# Arch_Max.net
KiCad netlist of a schematic drawn in EAGLE
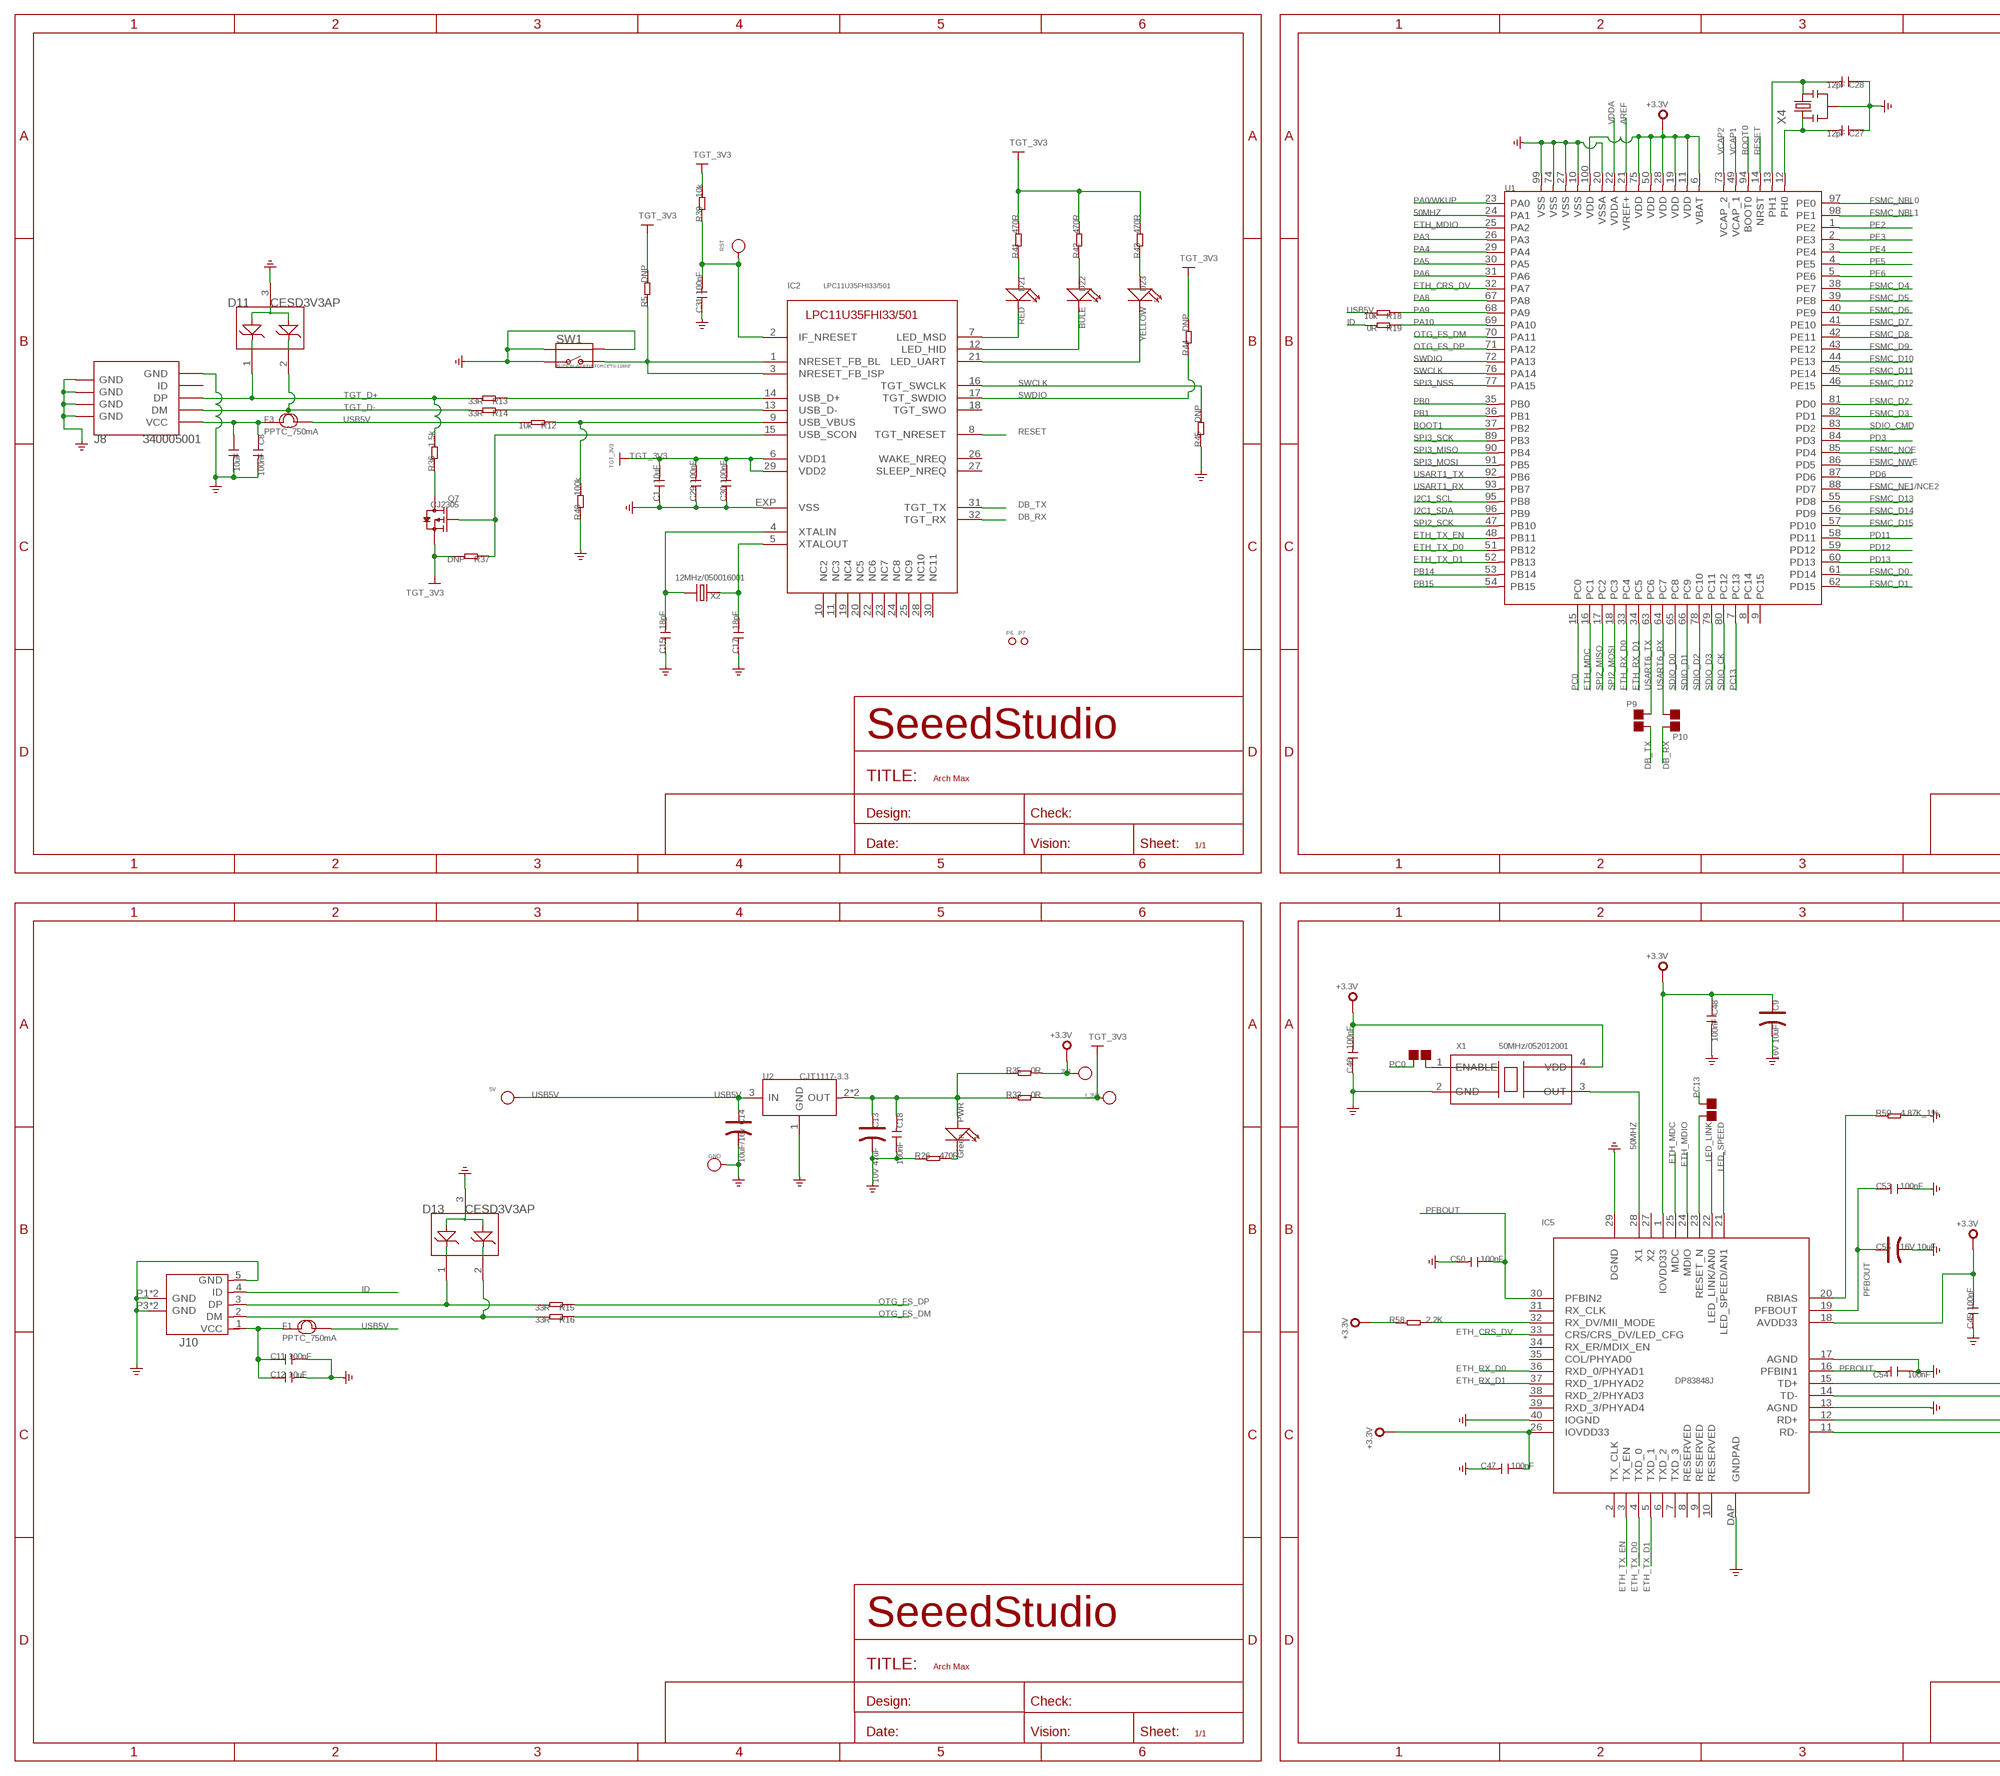
[diagram p0: schematic, sheet 1, part 1 of 2]
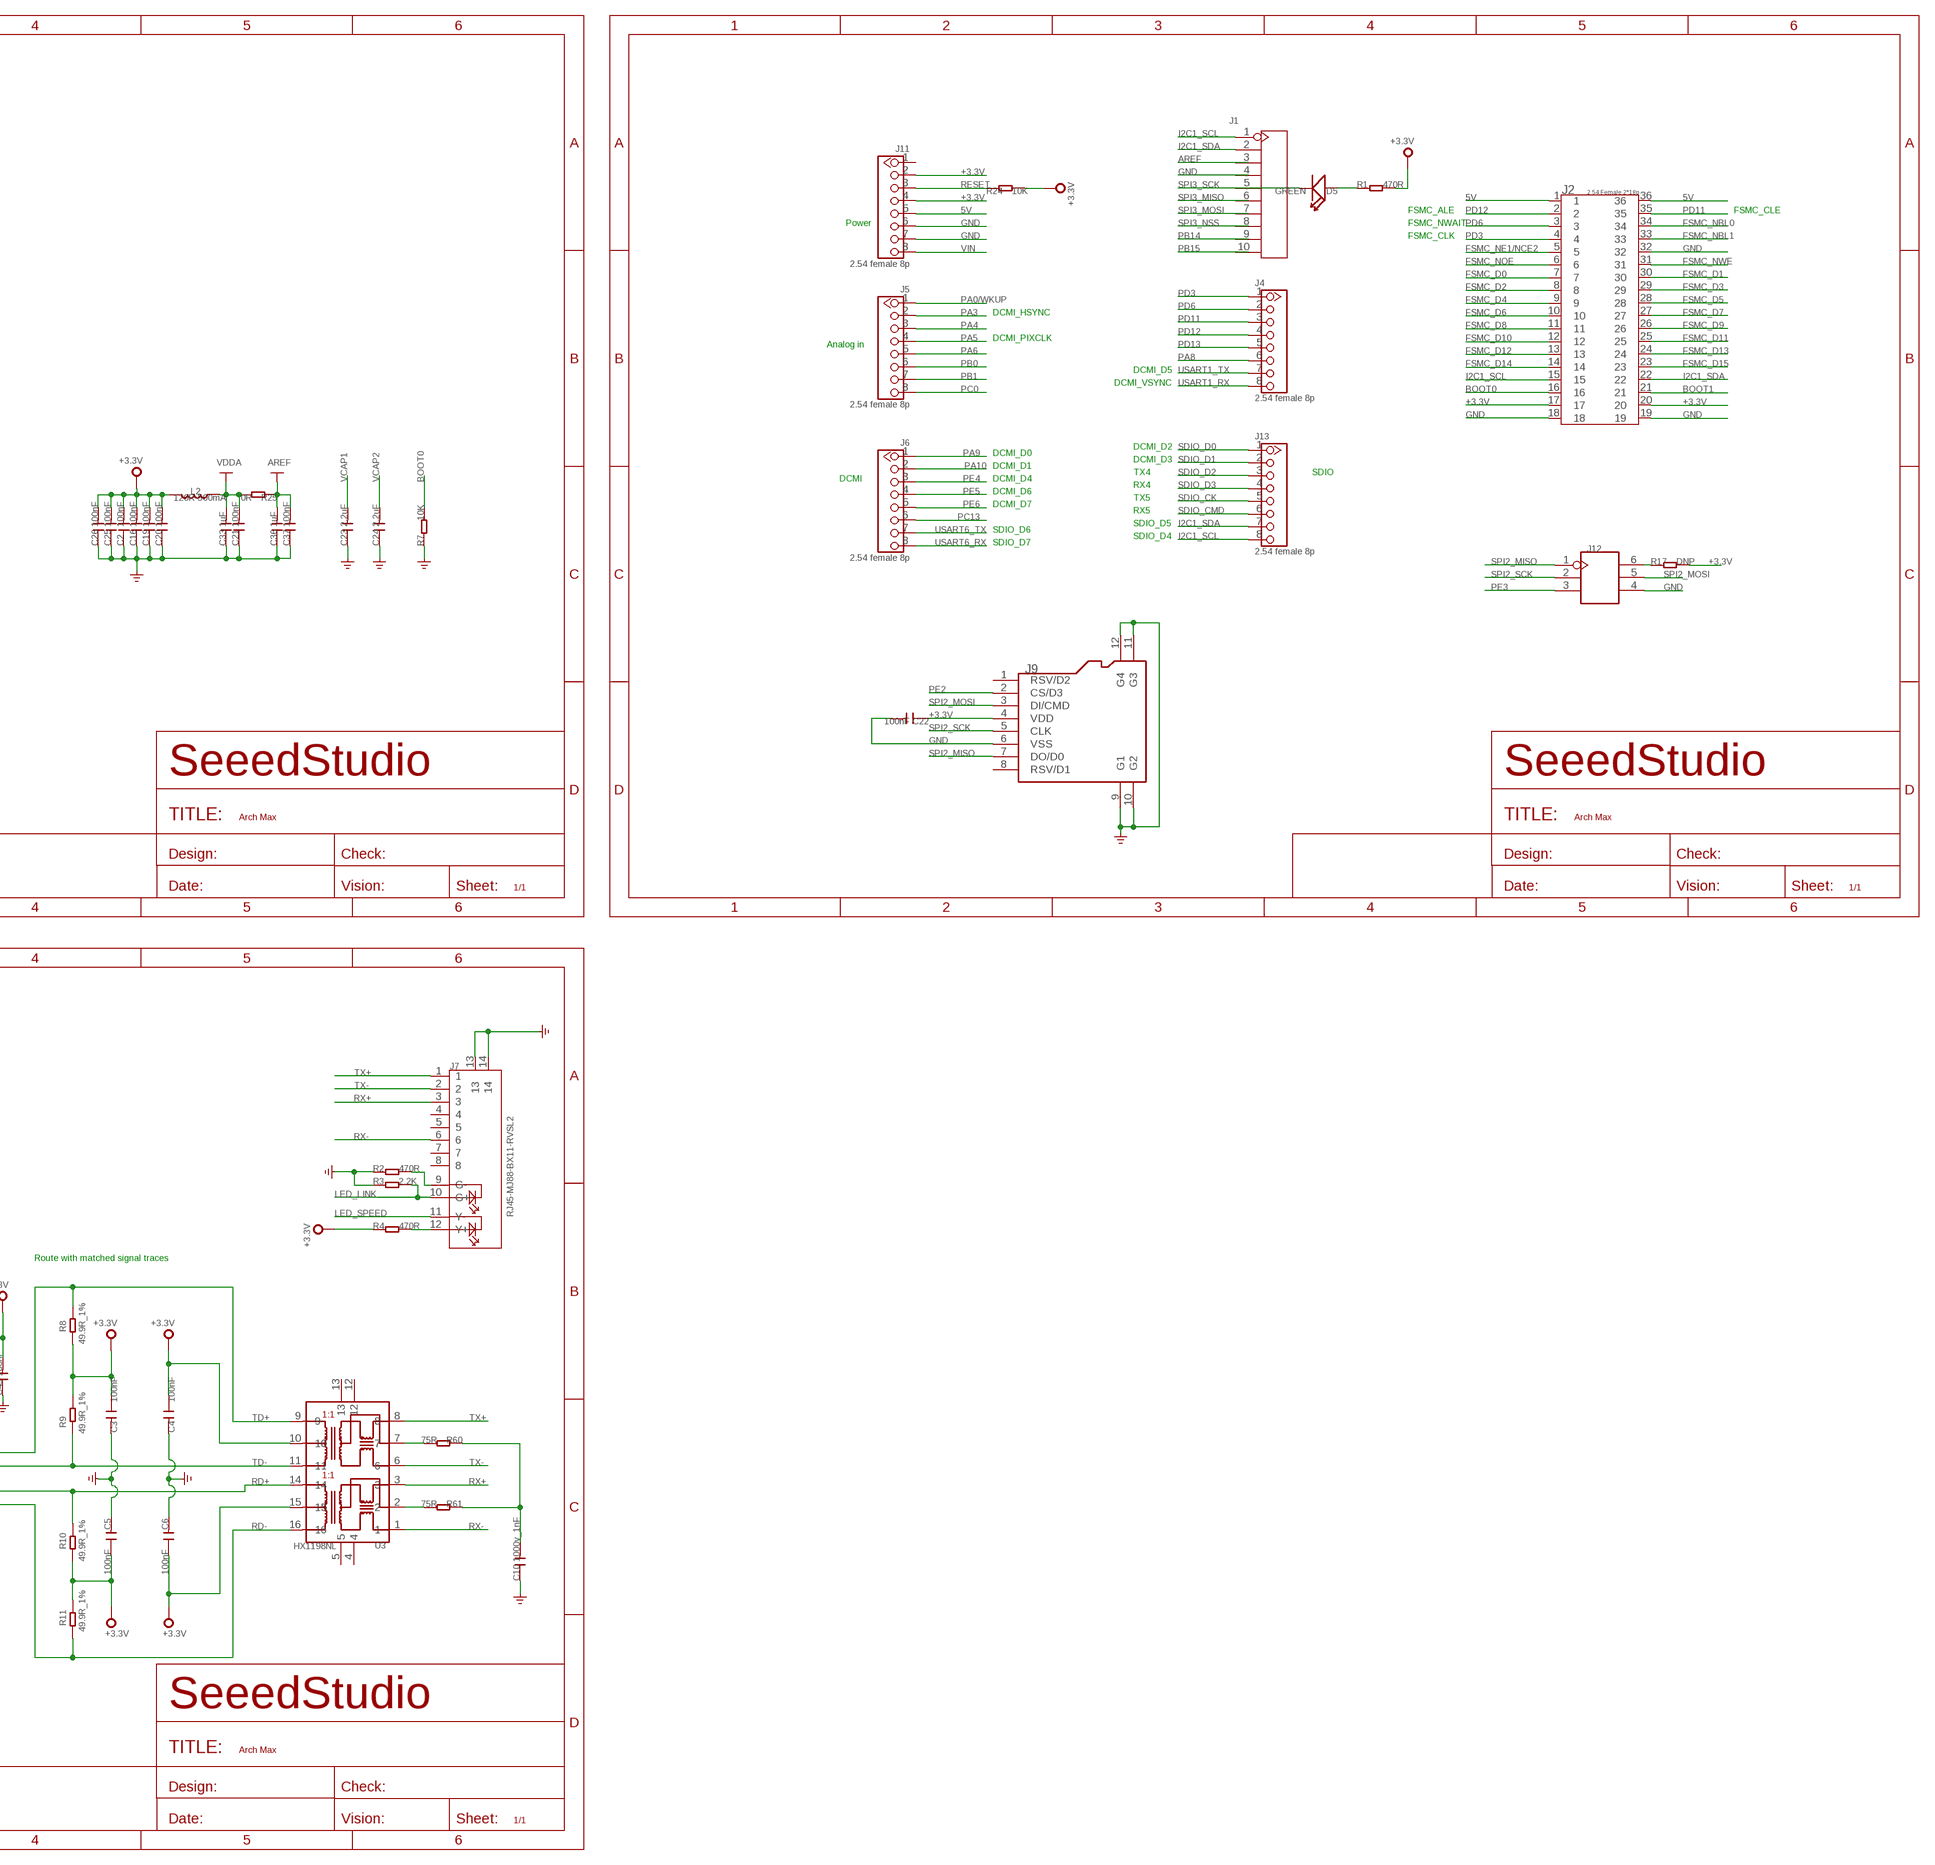
[diagram p1: schematic, sheet 1, part 2 of 2]

(export (version "E")
  (design (tool "Eeschema 10.0.6"))
  (components
    (comp (ref "3V3")
      (value "PAD-TEST-POINT'4545'")
      (footprint "eagle-import:TP_4545")
      (fields (field (name "PARTNO") "DNP"))
      (libsource (lib "eagle-import") (part "PAD-TEST-POINT'4545'"))
    )
    (comp (ref "5V")
      (value "PAD-TEST-POINT'4545'")
      (footprint "eagle-import:TP_4545")
      (fields (field (name "PARTNO") "DNP"))
      (libsource (lib "eagle-import") (part "PAD-TEST-POINT'4545'"))
    )
    (comp (ref "C1")
      (value "10uF")
      (footprint "eagle-import:C0805")
      (libsource (lib "eagle-import") (part "C-0805"))
    )
    (comp (ref "C2")
      (value "100nF")
      (footprint "eagle-import:C0603")
      (libsource (lib "eagle-import") (part "C-0603"))
    )
    (comp (ref "C3")
      (value "100nF")
      (footprint "eagle-import:C0603")
      (libsource (lib "eagle-import") (part "C-0603"))
    )
    (comp (ref "C4")
      (value "100nF")
      (footprint "eagle-import:C0603")
      (libsource (lib "eagle-import") (part "C-0603"))
    )
    (comp (ref "C5")
      (value "100nF")
      (footprint "eagle-import:C0603")
      (libsource (lib "eagle-import") (part "C-0603"))
    )
    (comp (ref "C6")
      (value "100nF")
      (footprint "eagle-import:C0603")
      (libsource (lib "eagle-import") (part "C-0603"))
    )
    (comp (ref "C7")
      (value "10uF")
      (footprint "eagle-import:C0805")
      (libsource (lib "eagle-import") (part "C-0805"))
    )
    (comp (ref "C8")
      (value "100nF")
      (footprint "eagle-import:C0603")
      (libsource (lib "eagle-import") (part "C-0603"))
    )
    (comp (ref "C9")
      (value "16V 10uF")
      (footprint "eagle-import:AVX-A")
      (libsource (lib "eagle-import") (part "CAP-AVX-A"))
    )
    (comp (ref "C10")
      (value "1000v_1nF")
      (footprint "eagle-import:C1206")
      (libsource (lib "eagle-import") (part "C-1206"))
    )
    (comp (ref "C11")
      (value "100nF")
      (footprint "eagle-import:C0603")
      (libsource (lib "eagle-import") (part "C-0603"))
    )
    (comp (ref "C12")
      (value "10uF")
      (footprint "eagle-import:C0805")
      (libsource (lib "eagle-import") (part "C-0805"))
    )
    (comp (ref "C13")
      (value "10V 47uF")
      (footprint "eagle-import:AVX-B")
      (libsource (lib "eagle-import") (part "CAP-AVX-B"))
    )
    (comp (ref "C14")
      (value "10uF/16v")
      (footprint "eagle-import:AVX-A")
      (libsource (lib "eagle-import") (part "CAP-AVX-A"))
    )
    (comp (ref "C15")
      (value "18pF")
      (footprint "eagle-import:C0603")
      (libsource (lib "eagle-import") (part "C-0603"))
    )
    (comp (ref "C16")
      (value "100nF")
      (footprint "eagle-import:C0603")
      (libsource (lib "eagle-import") (part "C-0603"))
    )
    (comp (ref "C17")
      (value "18pF")
      (footprint "eagle-import:C0603")
      (libsource (lib "eagle-import") (part "C-0603"))
    )
    (comp (ref "C18")
      (value "100nF")
      (footprint "eagle-import:C0603")
      (libsource (lib "eagle-import") (part "C-0603"))
    )
    (comp (ref "C19")
      (value "100nF")
      (footprint "eagle-import:C0603")
      (libsource (lib "eagle-import") (part "C-0603"))
    )
    (comp (ref "C20")
      (value "100nF")
      (footprint "eagle-import:C0603")
      (libsource (lib "eagle-import") (part "C-0603"))
    )
    (comp (ref "C21")
      (value "100nF")
      (footprint "eagle-import:C0603")
      (libsource (lib "eagle-import") (part "C-0603"))
    )
    (comp (ref "C22")
      (value "100nF")
      (footprint "eagle-import:C0603")
      (libsource (lib "eagle-import") (part "C-0603"))
    )
    (comp (ref "C23")
      (value "2.2uF")
      (footprint "eagle-import:C0603")
      (libsource (lib "eagle-import") (part "C-0603"))
    )
    (comp (ref "C24")
      (value "2.2uF")
      (footprint "eagle-import:C0603")
      (libsource (lib "eagle-import") (part "C-0603"))
    )
    (comp (ref "C25")
      (value "100nF")
      (footprint "eagle-import:C0603")
      (libsource (lib "eagle-import") (part "C-0603"))
    )
    (comp (ref "C26")
      (value "100nF")
      (footprint "eagle-import:C0603")
      (libsource (lib "eagle-import") (part "C-0603"))
    )
    (comp (ref "C27")
      (value "12pF")
      (footprint "eagle-import:C0603")
      (libsource (lib "eagle-import") (part "C-0603"))
    )
    (comp (ref "C28")
      (value "12pF")
      (footprint "eagle-import:C0603")
      (libsource (lib "eagle-import") (part "C-0603"))
    )
    (comp (ref "C29")
      (value "100nF")
      (footprint "eagle-import:C0603")
      (libsource (lib "eagle-import") (part "C-0603"))
    )
    (comp (ref "C30")
      (value "100nF")
      (footprint "eagle-import:C0603")
      (libsource (lib "eagle-import") (part "C-0603"))
    )
    (comp (ref "C31")
      (value "100nF")
      (footprint "eagle-import:C0603")
      (libsource (lib "eagle-import") (part "C-0603"))
    )
    (comp (ref "C33")
      (value "1uF")
      (footprint "eagle-import:C0603")
      (libsource (lib "eagle-import") (part "C-0603"))
    )
    (comp (ref "C36")
      (value "1uF")
      (footprint "eagle-import:C0603")
      (libsource (lib "eagle-import") (part "C-0603"))
    )
    (comp (ref "C37")
      (value "100nF")
      (footprint "eagle-import:C0603")
      (libsource (lib "eagle-import") (part "C-0603"))
    )
    (comp (ref "C45")
      (value "100nF")
      (footprint "eagle-import:C0603")
      (libsource (lib "eagle-import") (part "C-0603"))
    )
    (comp (ref "C46")
      (value "100nF")
      (footprint "eagle-import:C0603")
      (libsource (lib "eagle-import") (part "C-0603"))
    )
    (comp (ref "C47")
      (value "100nF")
      (footprint "eagle-import:C0603")
      (libsource (lib "eagle-import") (part "C-0603"))
    )
    (comp (ref "C48")
      (value "100nF")
      (footprint "eagle-import:C0603")
      (libsource (lib "eagle-import") (part "C-0603"))
    )
    (comp (ref "C50")
      (value "100nF")
      (footprint "eagle-import:C0603")
      (libsource (lib "eagle-import") (part "C-0603"))
    )
    (comp (ref "C53")
      (value "100nF")
      (footprint "eagle-import:C0603")
      (libsource (lib "eagle-import") (part "C-0603"))
    )
    (comp (ref "C54")
      (value "100nF")
      (footprint "eagle-import:C0603")
      (libsource (lib "eagle-import") (part "C-0603"))
    )
    (comp (ref "C55")
      (value "16V 10uF")
      (footprint "eagle-import:AVX-A")
      (libsource (lib "eagle-import") (part "CAP-AVX-A"))
    )
    (comp (ref "D5")
      (value "GREEN")
      (footprint "eagle-import:LED-0603")
      (libsource (lib "eagle-import") (part "LED'0603'"))
    )
    (comp (ref "D11")
      (value "CESD3V3AP")
      (footprint "eagle-import:SOT23")
      (libsource (lib "eagle-import") (part "D-ESD-3P"))
    )
    (comp (ref "D13")
      (value "CESD3V3AP")
      (footprint "eagle-import:SOT23")
      (libsource (lib "eagle-import") (part "D-ESD-3P"))
    )
    (comp (ref "D21")
      (value "RED")
      (footprint "eagle-import:LED-0603")
      (libsource (lib "eagle-import") (part "LED'0603'"))
    )
    (comp (ref "D22")
      (value "BULE")
      (footprint "eagle-import:LED-0603")
      (libsource (lib "eagle-import") (part "LED'0603'"))
    )
    (comp (ref "D23")
      (value "YELLOW")
      (footprint "eagle-import:LED-0603")
      (libsource (lib "eagle-import") (part "LED'0603'"))
    )
    (comp (ref "F1")
      (value "PPTC_750mA")
      (footprint "eagle-import:F1206")
      (libsource (lib "eagle-import") (part "FUSE'1206'"))
    )
    (comp (ref "F3")
      (value "PPTC_750mA")
      (footprint "eagle-import:F1206")
      (libsource (lib "eagle-import") (part "FUSE'1206'"))
    )
    (comp (ref "GND")
      (value "PAD-TEST-POINT'4545'")
      (footprint "eagle-import:TP_4545")
      (fields (field (name "PARTNO") "DNP"))
      (libsource (lib "eagle-import") (part "PAD-TEST-POINT'4545'"))
    )
    (comp (ref "IC2")
      (value "LPC11U35FHI33/501")
      (footprint "eagle-import:MBED-ICS_HVQFN33")
      (libsource (lib "eagle-import") (part "MBED-ICS_IF-LPC11U35"))
    )
    (comp (ref "IC5")
      (value "DP83848J")
      (footprint "eagle-import:LLP-40")
      (libsource (lib "eagle-import") (part "DP83848J"))
    )
    (comp (ref "I_3V3")
      (value "PAD-TEST-POINT'4545'")
      (footprint "eagle-import:TP_4545")
      (fields (field (name "PARTNO") "DNP"))
      (libsource (lib "eagle-import") (part "PAD-TEST-POINT'4545'"))
    )
    (comp (ref "J1")
      (value "HEADER-10P-2.54")
      (footprint "eagle-import:10P-2.54-65_35MIL")
      (libsource (lib "eagle-import") (part "HEADER-10P-2.54"))
    )
    (comp (ref "J2")
      (value "2.54 Female 2*18p")
      (footprint "eagle-import:2.54-2X18P")
      (libsource (lib "eagle-import") (part "HEADER-2X18P"))
    )
    (comp (ref "J4")
      (value "2.54 female 8p")
      (footprint "eagle-import:CK_1X8")
      (libsource (lib "eagle-import") (part "HEADER-8P2.54"))
    )
    (comp (ref "J5")
      (value "2.54 female 8p")
      (footprint "eagle-import:CK_1X8")
      (libsource (lib "eagle-import") (part "HEADER-8P2.54"))
    )
    (comp (ref "J6")
      (value "2.54 female 8p")
      (footprint "eagle-import:CK_1X8")
      (libsource (lib "eagle-import") (part "HEADER-8P2.54"))
    )
    (comp (ref "J7")
      (value "RJ45-MJ88-BX11-RVSL2")
      (footprint "eagle-import:RJ45-MJ88-BX11-RVSL2")
      (libsource (lib "eagle-import") (part "RJ45-MJ88-BX11-RVSL2"))
    )
    (comp (ref "J8")
      (value "340005001")
      (footprint "eagle-import:MICRO-USB")
      (libsource (lib "eagle-import") (part "USB-MINIUSB-5P-MICRO"))
    )
    (comp (ref "J9")
      (value "HOLDER-MICROSD-8P")
      (footprint "eagle-import:8P-SMD")
      (libsource (lib "eagle-import") (part "HOLDER-MICROSD-8P"))
    )
    (comp (ref "J10")
      (value "USB-MICRO-5P'AB'")
      (footprint "eagle-import:MICRO-USB-5P-AB")
      (libsource (lib "eagle-import") (part "USB-MICRO-5P'AB'"))
    )
    (comp (ref "J11")
      (value "2.54 female 8p")
      (footprint "eagle-import:CK_1X8")
      (libsource (lib "eagle-import") (part "HEADER-8P2.54"))
    )
    (comp (ref "J12")
      (value "HEADER-2X3P-65/35MIL")
      (footprint "eagle-import:2X3P-2.54-65_35MIL")
      (libsource (lib "eagle-import") (part "HEADER-2X3P-65/35MIL"))
    )
    (comp (ref "J13")
      (value "2.54 female 8p")
      (footprint "eagle-import:CK_1X8")
      (libsource (lib "eagle-import") (part "HEADER-8P2.54"))
    )
    (comp (ref "L2")
      (value "120R-500mA")
      (footprint "eagle-import:L0603")
      (libsource (lib "eagle-import") (part "L'0603'"))
    )
    (comp (ref "P1")
      (value "PAD-JUMPER-2P")
      (footprint "eagle-import:2P-SMD-1.78X1.27")
      (fields (field (name "PARTNO") "DNP"))
      (libsource (lib "eagle-import") (part "PAD-JUMPER-2P"))
    )
    (comp (ref "P5")
      (value "PAD-JUMPER-2P")
      (footprint "eagle-import:2P-SMD-1.78X1.27")
      (fields (field (name "PARTNO") "DNP"))
      (libsource (lib "eagle-import") (part "PAD-JUMPER-2P"))
    )
    (comp (ref "P6")
      (value "PAD-MARK'ANNULAR'")
      (footprint "eagle-import:ROUND-MARK-1.0")
      (fields (field (name "PARTNO") "DNP"))
      (libsource (lib "eagle-import") (part "PAD-MARK'ANNULAR'"))
    )
    (comp (ref "P7")
      (value "PAD-MARK'ANNULAR'")
      (footprint "eagle-import:ROUND-MARK-1.0")
      (fields (field (name "PARTNO") "DNP"))
      (libsource (lib "eagle-import") (part "PAD-MARK'ANNULAR'"))
    )
    (comp (ref "P9")
      (value "PAD-JUMPER-2P")
      (footprint "eagle-import:2P-SMD-1.78X1.27")
      (fields (field (name "PARTNO") "DNP"))
      (libsource (lib "eagle-import") (part "PAD-JUMPER-2P"))
    )
    (comp (ref "P10")
      (value "PAD-JUMPER-2P")
      (footprint "eagle-import:2P-SMD-1.78X1.27")
      (fields (field (name "PARTNO") "DNP"))
      (libsource (lib "eagle-import") (part "PAD-JUMPER-2P"))
    )
    (comp (ref "PWR")
      (value "Green")
      (footprint "eagle-import:LED-0603")
      (libsource (lib "eagle-import") (part "LED'0603'"))
    )
    (comp (ref "Q7")
      (value "CJ2305")
      (footprint "eagle-import:SOT23")
      (libsource (lib "eagle-import") (part "MOSFET-P'SI2323CDS/SI2305DS{lt}BR{gt}'"))
    )
    (comp (ref "R1")
      (value "470R")
      (footprint "eagle-import:R0603")
      (libsource (lib "eagle-import") (part "R-0603"))
    )
    (comp (ref "R2")
      (value "470R")
      (footprint "eagle-import:R0603")
      (libsource (lib "eagle-import") (part "R-0603"))
    )
    (comp (ref "R3")
      (value "2.2K")
      (footprint "eagle-import:R0603")
      (libsource (lib "eagle-import") (part "R-0603"))
    )
    (comp (ref "R4")
      (value "470R")
      (footprint "eagle-import:R0603")
      (libsource (lib "eagle-import") (part "R-0603"))
    )
    (comp (ref "R5")
      (value "DNP")
      (footprint "eagle-import:R0603")
      (libsource (lib "eagle-import") (part "R-0603"))
    )
    (comp (ref "R7")
      (value "10K")
      (footprint "eagle-import:R0603")
      (libsource (lib "eagle-import") (part "R-0603"))
    )
    (comp (ref "R8")
      (value "49.9R_1%")
      (footprint "eagle-import:R0603")
      (libsource (lib "eagle-import") (part "R-0603"))
    )
    (comp (ref "R9")
      (value "49.9R_1%")
      (footprint "eagle-import:R0603")
      (libsource (lib "eagle-import") (part "R-0603"))
    )
    (comp (ref "R10")
      (value "49.9R_1%")
      (footprint "eagle-import:R0603")
      (libsource (lib "eagle-import") (part "R-0603"))
    )
    (comp (ref "R11")
      (value "49.9R_1%")
      (footprint "eagle-import:R0603")
      (libsource (lib "eagle-import") (part "R-0603"))
    )
    (comp (ref "R12")
      (value "10k")
      (footprint "eagle-import:R0603")
      (libsource (lib "eagle-import") (part "R-0603"))
    )
    (comp (ref "R13")
      (value "33R")
      (footprint "eagle-import:R0603")
      (libsource (lib "eagle-import") (part "R-0603"))
    )
    (comp (ref "R14")
      (value "33R")
      (footprint "eagle-import:R0603")
      (libsource (lib "eagle-import") (part "R-0603"))
    )
    (comp (ref "R15")
      (value "33R")
      (footprint "eagle-import:R0603")
      (libsource (lib "eagle-import") (part "R-0603"))
    )
    (comp (ref "R16")
      (value "33R")
      (footprint "eagle-import:R0603")
      (libsource (lib "eagle-import") (part "R-0603"))
    )
    (comp (ref "R17")
      (value "DNP")
      (footprint "eagle-import:R0603")
      (libsource (lib "eagle-import") (part "R-0603"))
    )
    (comp (ref "R18")
      (value "10k")
      (footprint "eagle-import:R0603")
      (libsource (lib "eagle-import") (part "R-0603"))
    )
    (comp (ref "R19")
      (value "0R")
      (footprint "eagle-import:R0603")
      (libsource (lib "eagle-import") (part "R-0603"))
    )
    (comp (ref "R24")
      (value "10K")
      (footprint "eagle-import:R0603")
      (libsource (lib "eagle-import") (part "R-0603"))
    )
    (comp (ref "R25")
      (value "0R")
      (footprint "eagle-import:R0603")
      (libsource (lib "eagle-import") (part "R-0603"))
    )
    (comp (ref "R26")
      (value "470R")
      (footprint "eagle-import:R0603")
      (libsource (lib "eagle-import") (part "R-0603"))
    )
    (comp (ref "R33")
      (value "0R")
      (footprint "eagle-import:R0603")
      (libsource (lib "eagle-import") (part "R-0603"))
    )
    (comp (ref "R35")
      (value "0R")
      (footprint "eagle-import:R0603")
      (libsource (lib "eagle-import") (part "R-0603"))
    )
    (comp (ref "R36")
      (value "1.5k")
      (footprint "eagle-import:R0603")
      (libsource (lib "eagle-import") (part "R-0603"))
    )
    (comp (ref "R37")
      (value "DNP")
      (footprint "eagle-import:R0603")
      (libsource (lib "eagle-import") (part "R-0603"))
    )
    (comp (ref "R39")
      (value "10k")
      (footprint "eagle-import:R0603")
      (libsource (lib "eagle-import") (part "R-0603"))
    )
    (comp (ref "R40")
      (value "100k")
      (footprint "eagle-import:R0603")
      (libsource (lib "eagle-import") (part "R-0603"))
    )
    (comp (ref "R41")
      (value "470R")
      (footprint "eagle-import:R0603")
      (libsource (lib "eagle-import") (part "R-0603"))
    )
    (comp (ref "R42")
      (value "470R")
      (footprint "eagle-import:R0603")
      (libsource (lib "eagle-import") (part "R-0603"))
    )
    (comp (ref "R43")
      (value "470R")
      (footprint "eagle-import:R0603")
      (libsource (lib "eagle-import") (part "R-0603"))
    )
    (comp (ref "R44")
      (value "DNP")
      (footprint "eagle-import:R0603")
      (libsource (lib "eagle-import") (part "R-0603"))
    )
    (comp (ref "R45")
      (value "DNP")
      (footprint "eagle-import:R0603")
      (libsource (lib "eagle-import") (part "R-0603"))
    )
    (comp (ref "R58")
      (value "2.2K")
      (footprint "eagle-import:R0603")
      (libsource (lib "eagle-import") (part "R-0603"))
    )
    (comp (ref "R59")
      (value "4.87K_1%")
      (footprint "eagle-import:R0603")
      (libsource (lib "eagle-import") (part "R-0603"))
    )
    (comp (ref "R60")
      (value "75R")
      (footprint "eagle-import:R0603")
      (libsource (lib "eagle-import") (part "R-0603"))
    )
    (comp (ref "R61")
      (value "75R")
      (footprint "eagle-import:R0603")
      (libsource (lib "eagle-import") (part "R-0603"))
    )
    (comp (ref "RST")
      (value "PAD-TEST-POINT'4545'")
      (footprint "eagle-import:TP_4545")
      (fields (field (name "PARTNO") "DNP"))
      (libsource (lib "eagle-import") (part "PAD-TEST-POINT'4545'"))
    )
    (comp (ref "SW1")
      (value "BUTTON-4P-REINFORCE'TS-1188E'")
      (footprint "eagle-import:4P-SMD-7X3.5X3.5H")
      (libsource (lib "eagle-import") (part "BUTTON-4P-REINFORCE'TS-1188E'"))
    )
    (comp (ref "U1")
      (value "STM32F407VET6")
      (footprint "eagle-import:LQFP100")
      (libsource (lib "eagle-import") (part "STM32F407VET6"))
    )
    (comp (ref "U2")
      (value "CJT1117-3.3")
      (footprint "eagle-import:SOT-223")
      (libsource (lib "eagle-import") (part "LD1117S"))
    )
    (comp (ref "U3")
      (value "HX1198NL")
      (footprint "eagle-import:SOIC16-9.53")
      (libsource (lib "eagle-import") (part "HX1198NL"))
    )
    (comp (ref "X1")
      (value "50MHz/052012001")
      (footprint "eagle-import:4P-SMD-5X3.2")
      (libsource (lib "eagle-import") (part "CRYSTAL-SPXO"))
    )
    (comp (ref "X2")
      (value "12MHz/050016001")
      (footprint "eagle-import:2P-SMD-5X3.2")
      (libsource (lib "eagle-import") (part "CRYSTAL'5032'"))
    )
    (comp (ref "X4")
      (value "CRYSTAL-RESONATOR'SMD'")
      (footprint "eagle-import:3P-SMD-3.6X1.3")
      (libsource (lib "eagle-import") (part "CRYSTAL-RESONATOR'SMD'"))
    )
  )
  (nets
    (net (code "1") (name "+3.3V") (class "Default")
      (node (ref "3V3") (pin "T") (pinfunction "T_T") (pintype "bidirectional"))
      (node (ref "C16") (pin "2") (pinfunction "2_2") (pintype "passive"))
      (node (ref "C19") (pin "2") (pinfunction "2_2") (pintype "passive"))
      (node (ref "C2") (pin "2") (pinfunction "2_2") (pintype "passive"))
      (node (ref "C20") (pin "2") (pinfunction "2_2") (pintype "passive"))
      (node (ref "C22") (pin "1") (pinfunction "1_1") (pintype "passive"))
      (node (ref "C25") (pin "2") (pinfunction "2_2") (pintype "passive"))
      (node (ref "C26") (pin "2") (pinfunction "2_2") (pintype "passive"))
      (node (ref "C3") (pin "1") (pinfunction "1_1") (pintype "passive"))
      (node (ref "C4") (pin "1") (pinfunction "1_1") (pintype "passive"))
      (node (ref "C45") (pin "2") (pinfunction "2_2") (pintype "passive"))
      (node (ref "C46") (pin "2") (pinfunction "2_2") (pintype "passive"))
      (node (ref "C47") (pin "1") (pinfunction "1_1") (pintype "passive"))
      (node (ref "C48") (pin "1") (pinfunction "1_1") (pintype "passive"))
      (node (ref "C5") (pin "1") (pinfunction "1_1") (pintype "passive"))
      (node (ref "C6") (pin "1") (pinfunction "1_1") (pintype "passive"))
      (node (ref "C9") (pin "+") (pinfunction "+_+") (pintype "passive"))
      (node (ref "IC5") (pin "1") (pinfunction "IOVDD33_1") (pintype "power_in"))
      (node (ref "IC5") (pin "18") (pinfunction "AVDD33_18") (pintype "power_in"))
      (node (ref "IC5") (pin "26") (pinfunction "IOVDD33_26") (pintype "power_in"))
      (node (ref "J11") (pin "2") (pinfunction "2_2") (pintype "bidirectional"))
      (node (ref "J11") (pin "4") (pinfunction "4_4") (pintype "bidirectional"))
      (node (ref "J2") (pin "17") (pinfunction "17_17") (pintype "bidirectional"))
      (node (ref "J2") (pin "20") (pinfunction "20_20") (pintype "bidirectional"))
      (node (ref "J9") (pin "4") (pinfunction "VDD_4") (pintype "bidirectional"))
      (node (ref "L2") (pin "2") (pinfunction "2_2") (pintype "passive"))
      (node (ref "R1") (pin "2") (pinfunction "2_2") (pintype "passive"))
      (node (ref "R10") (pin "1") (pinfunction "1_1") (pintype "passive"))
      (node (ref "R11") (pin "2") (pinfunction "2_2") (pintype "passive"))
      (node (ref "R17") (pin "2") (pinfunction "2_2") (pintype "passive"))
      (node (ref "R24") (pin "2") (pinfunction "2_2") (pintype "passive"))
      (node (ref "R35") (pin "1") (pinfunction "1_1") (pintype "passive"))
      (node (ref "R4") (pin "1") (pinfunction "1_1") (pintype "passive"))
      (node (ref "R58") (pin "1") (pinfunction "1_1") (pintype "passive"))
      (node (ref "R8") (pin "1") (pinfunction "1_1") (pintype "passive"))
      (node (ref "R9") (pin "2") (pinfunction "2_2") (pintype "passive"))
      (node (ref "U1") (pin "100") (pinfunction "VDD_100") (pintype "bidirectional"))
      (node (ref "U1") (pin "11") (pinfunction "VDD_11") (pintype "bidirectional"))
      (node (ref "U1") (pin "19") (pinfunction "VDD_19") (pintype "bidirectional"))
      (node (ref "U1") (pin "28") (pinfunction "VDD_28") (pintype "bidirectional"))
      (node (ref "U1") (pin "50") (pinfunction "VDD_50") (pintype "bidirectional"))
      (node (ref "U1") (pin "6") (pinfunction "VBAT_6") (pintype "bidirectional"))
      (node (ref "U1") (pin "75") (pinfunction "VDD_75") (pintype "bidirectional"))
      (node (ref "U3") (pin "10") (pinfunction "10_10") (pintype "bidirectional"))
      (node (ref "U3") (pin "15") (pinfunction "15_15") (pintype "bidirectional"))
      (node (ref "X1") (pin "4") (pinfunction "VDD_4") (pintype "bidirectional"))
    )
    (net (code "2") (name "/5V") (class "Default")
      (node (ref "J11") (pin "5") (pinfunction "5_5") (pintype "bidirectional"))
      (node (ref "J2") (pin "1") (pinfunction "1_1") (pintype "bidirectional"))
      (node (ref "J2") (pin "36") (pinfunction "36_36") (pintype "bidirectional"))
    )
    (net (code "3") (name "/50MHZ") (class "Default")
      (node (ref "IC5") (pin "28") (pinfunction "X1_28") (pintype "passive"))
      (node (ref "U1") (pin "24") (pinfunction "PA1_24") (pintype "bidirectional"))
      (node (ref "X1") (pin "3") (pinfunction "OUT_3") (pintype "bidirectional"))
    )
    (net (code "4") (name "/BOOT0") (class "Default")
      (node (ref "J2") (pin "16") (pinfunction "16_16") (pintype "bidirectional"))
      (node (ref "R7") (pin "2") (pinfunction "2_2") (pintype "passive"))
      (node (ref "U1") (pin "94") (pinfunction "BOOT0_94") (pintype "bidirectional"))
    )
    (net (code "5") (name "/BOOT1") (class "Default")
      (node (ref "J2") (pin "21") (pinfunction "21_21") (pintype "bidirectional"))
      (node (ref "U1") (pin "37") (pinfunction "PB2_37") (pintype "bidirectional"))
    )
    (net (code "6") (name "/DB_RX") (class "Default")
      (node (ref "IC2") (pin "32") (pinfunction "TGT_RX_32") (pintype "bidirectional"))
      (node (ref "P10") (pin "2") (pinfunction "2_2") (pintype "bidirectional"))
    )
    (net (code "7") (name "/DB_TX") (class "Default")
      (node (ref "IC2") (pin "31") (pinfunction "TGT_TX_31") (pintype "bidirectional"))
      (node (ref "P9") (pin "1") (pinfunction "1_1") (pintype "bidirectional"))
    )
    (net (code "8") (name "/ETH_CRS_DV") (class "Default")
      (node (ref "IC5") (pin "33") (pinfunction "CRS/CRS_DV/LED_CFG_33") (pintype "output"))
      (node (ref "U1") (pin "32") (pinfunction "PA7_32") (pintype "bidirectional"))
    )
    (net (code "9") (name "/ETH_MDC") (class "Default")
      (node (ref "IC5") (pin "25") (pinfunction "MDC_25") (pintype "input"))
      (node (ref "U1") (pin "16") (pinfunction "PC1_16") (pintype "bidirectional"))
    )
    (net (code "10") (name "/ETH_MDIO") (class "Default")
      (node (ref "IC5") (pin "24") (pinfunction "MDIO_24") (pintype "bidirectional"))
      (node (ref "U1") (pin "25") (pinfunction "PA2_25") (pintype "bidirectional"))
    )
    (net (code "11") (name "/ETH_RX_D0") (class "Default")
      (node (ref "IC5") (pin "36") (pinfunction "RXD_0/PHYAD1_36") (pintype "output"))
      (node (ref "U1") (pin "33") (pinfunction "PC4_33") (pintype "bidirectional"))
    )
    (net (code "12") (name "/ETH_RX_D1") (class "Default")
      (node (ref "IC5") (pin "37") (pinfunction "RXD_1/PHYAD2_37") (pintype "output"))
      (node (ref "U1") (pin "34") (pinfunction "PC5_34") (pintype "bidirectional"))
    )
    (net (code "13") (name "/ETH_TX_D0") (class "Default")
      (node (ref "IC5") (pin "4") (pinfunction "TXD_0_4") (pintype "input"))
      (node (ref "U1") (pin "51") (pinfunction "PB12_51") (pintype "bidirectional"))
    )
    (net (code "14") (name "/ETH_TX_D1") (class "Default")
      (node (ref "IC5") (pin "5") (pinfunction "TXD_1_5") (pintype "input"))
      (node (ref "U1") (pin "52") (pinfunction "PB13_52") (pintype "bidirectional"))
    )
    (net (code "15") (name "/ETH_TX_EN") (class "Default")
      (node (ref "IC5") (pin "3") (pinfunction "TX_EN_3") (pintype "input"))
      (node (ref "U1") (pin "48") (pinfunction "PB11_48") (pintype "bidirectional"))
    )
    (net (code "16") (name "/FSMC_D0") (class "Default")
      (node (ref "J2") (pin "7") (pinfunction "7_7") (pintype "bidirectional"))
      (node (ref "U1") (pin "61") (pinfunction "PD14_61") (pintype "bidirectional"))
    )
    (net (code "17") (name "/FSMC_D1") (class "Default")
      (node (ref "J2") (pin "30") (pinfunction "30_30") (pintype "bidirectional"))
      (node (ref "U1") (pin "62") (pinfunction "PD15_62") (pintype "bidirectional"))
    )
    (net (code "18") (name "/FSMC_D2") (class "Default")
      (node (ref "J2") (pin "8") (pinfunction "8_8") (pintype "bidirectional"))
      (node (ref "U1") (pin "81") (pinfunction "PD0_81") (pintype "bidirectional"))
    )
    (net (code "19") (name "/FSMC_D3") (class "Default")
      (node (ref "J2") (pin "29") (pinfunction "29_29") (pintype "bidirectional"))
      (node (ref "U1") (pin "82") (pinfunction "PD1_82") (pintype "bidirectional"))
    )
    (net (code "20") (name "/FSMC_D4") (class "Default")
      (node (ref "J2") (pin "9") (pinfunction "9_9") (pintype "bidirectional"))
      (node (ref "U1") (pin "38") (pinfunction "PE7_38") (pintype "bidirectional"))
    )
    (net (code "21") (name "/FSMC_D5") (class "Default")
      (node (ref "J2") (pin "28") (pinfunction "28_28") (pintype "bidirectional"))
      (node (ref "U1") (pin "39") (pinfunction "PE8_39") (pintype "bidirectional"))
    )
    (net (code "22") (name "/FSMC_D6") (class "Default")
      (node (ref "J2") (pin "10") (pinfunction "10_10") (pintype "bidirectional"))
      (node (ref "U1") (pin "40") (pinfunction "PE9_40") (pintype "bidirectional"))
    )
    (net (code "23") (name "/FSMC_D7") (class "Default")
      (node (ref "J2") (pin "27") (pinfunction "27_27") (pintype "bidirectional"))
      (node (ref "U1") (pin "41") (pinfunction "PE10_41") (pintype "bidirectional"))
    )
    (net (code "24") (name "/FSMC_D8") (class "Default")
      (node (ref "J2") (pin "11") (pinfunction "11_11") (pintype "bidirectional"))
      (node (ref "U1") (pin "42") (pinfunction "PE11_42") (pintype "bidirectional"))
    )
    (net (code "25") (name "/FSMC_D9") (class "Default")
      (node (ref "J2") (pin "26") (pinfunction "26_26") (pintype "bidirectional"))
      (node (ref "U1") (pin "43") (pinfunction "PE12_43") (pintype "bidirectional"))
    )
    (net (code "26") (name "/FSMC_D10") (class "Default")
      (node (ref "J2") (pin "12") (pinfunction "12_12") (pintype "bidirectional"))
      (node (ref "U1") (pin "44") (pinfunction "PE13_44") (pintype "bidirectional"))
    )
    (net (code "27") (name "/FSMC_D11") (class "Default")
      (node (ref "J2") (pin "25") (pinfunction "25_25") (pintype "bidirectional"))
      (node (ref "U1") (pin "45") (pinfunction "PE14_45") (pintype "bidirectional"))
    )
    (net (code "28") (name "/FSMC_D12") (class "Default")
      (node (ref "J2") (pin "13") (pinfunction "13_13") (pintype "bidirectional"))
      (node (ref "U1") (pin "46") (pinfunction "PE15_46") (pintype "bidirectional"))
    )
    (net (code "29") (name "/FSMC_D13") (class "Default")
      (node (ref "J2") (pin "24") (pinfunction "24_24") (pintype "bidirectional"))
      (node (ref "U1") (pin "55") (pinfunction "PD8_55") (pintype "bidirectional"))
    )
    (net (code "30") (name "/FSMC_D14") (class "Default")
      (node (ref "J2") (pin "14") (pinfunction "14_14") (pintype "bidirectional"))
      (node (ref "U1") (pin "56") (pinfunction "PD9_56") (pintype "bidirectional"))
    )
    (net (code "31") (name "/FSMC_D15") (class "Default")
      (node (ref "J2") (pin "23") (pinfunction "23_23") (pintype "bidirectional"))
      (node (ref "U1") (pin "57") (pinfunction "PD10_57") (pintype "bidirectional"))
    )
    (net (code "32") (name "/FSMC_NBL0") (class "Default")
      (node (ref "J2") (pin "34") (pinfunction "34_34") (pintype "bidirectional"))
      (node (ref "U1") (pin "97") (pinfunction "PE0_97") (pintype "bidirectional"))
    )
    (net (code "33") (name "/FSMC_NBL1") (class "Default")
      (node (ref "J2") (pin "33") (pinfunction "33_33") (pintype "bidirectional"))
      (node (ref "U1") (pin "98") (pinfunction "PE1_98") (pintype "bidirectional"))
    )
    (net (code "34") (name "/FSMC_NE1{slash}NCE2") (class "Default")
      (node (ref "J2") (pin "5") (pinfunction "5_5") (pintype "bidirectional"))
      (node (ref "U1") (pin "88") (pinfunction "PD7_88") (pintype "bidirectional"))
    )
    (net (code "35") (name "/FSMC_NOE") (class "Default")
      (node (ref "J2") (pin "6") (pinfunction "6_6") (pintype "bidirectional"))
      (node (ref "U1") (pin "85") (pinfunction "PD4_85") (pintype "bidirectional"))
    )
    (net (code "36") (name "/FSMC_NWE") (class "Default")
      (node (ref "J2") (pin "31") (pinfunction "31_31") (pintype "bidirectional"))
      (node (ref "U1") (pin "86") (pinfunction "PD5_86") (pintype "bidirectional"))
    )
    (net (code "37") (name "/I2C1_SCL") (class "Default")
      (node (ref "J1") (pin "1") (pinfunction "1_1") (pintype "bidirectional"))
      (node (ref "J13") (pin "8") (pinfunction "8_8") (pintype "bidirectional"))
      (node (ref "J2") (pin "15") (pinfunction "15_15") (pintype "bidirectional"))
      (node (ref "U1") (pin "95") (pinfunction "PB8_95") (pintype "bidirectional"))
    )
    (net (code "38") (name "/I2C1_SDA") (class "Default")
      (node (ref "J1") (pin "2") (pinfunction "2_2") (pintype "bidirectional"))
      (node (ref "J13") (pin "7") (pinfunction "7_7") (pintype "bidirectional"))
      (node (ref "J2") (pin "22") (pinfunction "22_22") (pintype "bidirectional"))
      (node (ref "U1") (pin "96") (pinfunction "PB9_96") (pintype "bidirectional"))
    )
    (net (code "39") (name "/ID") (class "Default")
      (node (ref "J10") (pin "4") (pinfunction "ID_4") (pintype "bidirectional"))
      (node (ref "R19") (pin "2") (pinfunction "2_2") (pintype "passive"))
    )
    (net (code "40") (name "/LED_LINK") (class "Default")
      (node (ref "IC5") (pin "22") (pinfunction "LED_LINK/AN0_22") (pintype "output"))
      (node (ref "J7") (pin "10") (pinfunction "G+_10") (pintype "bidirectional"))
      (node (ref "R3") (pin "2") (pinfunction "2_2") (pintype "passive"))
    )
    (net (code "41") (name "/LED_SPEED") (class "Default")
      (node (ref "IC5") (pin "21") (pinfunction "LED_SPEED/AN1_21") (pintype "output"))
      (node (ref "J7") (pin "11") (pinfunction "Y-_11") (pintype "bidirectional"))
    )
    (net (code "42") (name "/OTG_FS_DM") (class "Default")
      (node (ref "R16") (pin "1") (pinfunction "1_1") (pintype "passive"))
      (node (ref "U1") (pin "70") (pinfunction "PA11_70") (pintype "bidirectional"))
    )
    (net (code "43") (name "/OTG_FS_DP") (class "Default")
      (node (ref "R15") (pin "1") (pinfunction "1_1") (pintype "passive"))
      (node (ref "U1") (pin "71") (pinfunction "PA12_71") (pintype "bidirectional"))
    )
    (net (code "44") (name "/PA0{slash}WKUP") (class "Default")
      (node (ref "J5") (pin "1") (pinfunction "1_1") (pintype "bidirectional"))
      (node (ref "U1") (pin "23") (pinfunction "PA0_23") (pintype "bidirectional"))
    )
    (net (code "45") (name "/PA3") (class "Default")
      (node (ref "J5") (pin "2") (pinfunction "2_2") (pintype "bidirectional"))
      (node (ref "U1") (pin "26") (pinfunction "PA3_26") (pintype "bidirectional"))
    )
    (net (code "46") (name "/PA4") (class "Default")
      (node (ref "J5") (pin "3") (pinfunction "3_3") (pintype "bidirectional"))
      (node (ref "U1") (pin "29") (pinfunction "PA4_29") (pintype "bidirectional"))
    )
    (net (code "47") (name "/PA5") (class "Default")
      (node (ref "J5") (pin "4") (pinfunction "4_4") (pintype "bidirectional"))
      (node (ref "U1") (pin "30") (pinfunction "PA5_30") (pintype "bidirectional"))
    )
    (net (code "48") (name "/PA6") (class "Default")
      (node (ref "J5") (pin "5") (pinfunction "5_5") (pintype "bidirectional"))
      (node (ref "U1") (pin "31") (pinfunction "PA6_31") (pintype "bidirectional"))
    )
    (net (code "49") (name "/PA8") (class "Default")
      (node (ref "J4") (pin "6") (pinfunction "6_6") (pintype "bidirectional"))
      (node (ref "U1") (pin "67") (pinfunction "PA8_67") (pintype "bidirectional"))
    )
    (net (code "50") (name "/PA9") (class "Default")
      (node (ref "J6") (pin "1") (pinfunction "1_1") (pintype "bidirectional"))
      (node (ref "R18") (pin "1") (pinfunction "1_1") (pintype "passive"))
      (node (ref "U1") (pin "68") (pinfunction "PA9_68") (pintype "bidirectional"))
    )
    (net (code "51") (name "/PA10") (class "Default")
      (node (ref "J6") (pin "2") (pinfunction "2_2") (pintype "bidirectional"))
      (node (ref "R19") (pin "1") (pinfunction "1_1") (pintype "passive"))
      (node (ref "U1") (pin "69") (pinfunction "PA10_69") (pintype "bidirectional"))
    )
    (net (code "52") (name "/PB0") (class "Default")
      (node (ref "J5") (pin "6") (pinfunction "6_6") (pintype "bidirectional"))
      (node (ref "U1") (pin "35") (pinfunction "PB0_35") (pintype "bidirectional"))
    )
    (net (code "53") (name "/PB1") (class "Default")
      (node (ref "J5") (pin "7") (pinfunction "7_7") (pintype "bidirectional"))
      (node (ref "U1") (pin "36") (pinfunction "PB1_36") (pintype "bidirectional"))
    )
    (net (code "54") (name "/PB14") (class "Default")
      (node (ref "J1") (pin "9") (pinfunction "9_9") (pintype "bidirectional"))
      (node (ref "U1") (pin "53") (pinfunction "PB14_53") (pintype "bidirectional"))
    )
    (net (code "55") (name "/PB15") (class "Default")
      (node (ref "J1") (pin "10") (pinfunction "10_10") (pintype "bidirectional"))
      (node (ref "U1") (pin "54") (pinfunction "PB15_54") (pintype "bidirectional"))
    )
    (net (code "56") (name "/PC0") (class "Default")
      (node (ref "J5") (pin "8") (pinfunction "8_8") (pintype "bidirectional"))
      (node (ref "P5") (pin "1") (pinfunction "1_1") (pintype "bidirectional"))
      (node (ref "U1") (pin "15") (pinfunction "PC0_15") (pintype "bidirectional"))
    )
    (net (code "57") (name "/PC13") (class "Default")
      (node (ref "J6") (pin "6") (pinfunction "6_6") (pintype "bidirectional"))
      (node (ref "P1") (pin "1") (pinfunction "1_1") (pintype "bidirectional"))
      (node (ref "U1") (pin "7") (pinfunction "PC13_7") (pintype "bidirectional"))
    )
    (net (code "58") (name "/PD3") (class "Default")
      (node (ref "J2") (pin "4") (pinfunction "4_4") (pintype "bidirectional"))
      (node (ref "J4") (pin "1") (pinfunction "1_1") (pintype "bidirectional"))
      (node (ref "U1") (pin "84") (pinfunction "PD3_84") (pintype "bidirectional"))
    )
    (net (code "59") (name "/PD6") (class "Default")
      (node (ref "J2") (pin "3") (pinfunction "3_3") (pintype "bidirectional"))
      (node (ref "J4") (pin "2") (pinfunction "2_2") (pintype "bidirectional"))
      (node (ref "U1") (pin "87") (pinfunction "PD6_87") (pintype "bidirectional"))
    )
    (net (code "60") (name "/PD11") (class "Default")
      (node (ref "J2") (pin "35") (pinfunction "35_35") (pintype "bidirectional"))
      (node (ref "J4") (pin "3") (pinfunction "3_3") (pintype "bidirectional"))
      (node (ref "U1") (pin "58") (pinfunction "PD11_58") (pintype "bidirectional"))
    )
    (net (code "61") (name "/PD12") (class "Default")
      (node (ref "J2") (pin "2") (pinfunction "2_2") (pintype "bidirectional"))
      (node (ref "J4") (pin "4") (pinfunction "4_4") (pintype "bidirectional"))
      (node (ref "U1") (pin "59") (pinfunction "PD12_59") (pintype "bidirectional"))
    )
    (net (code "62") (name "/PD13") (class "Default")
      (node (ref "J4") (pin "5") (pinfunction "5_5") (pintype "bidirectional"))
      (node (ref "U1") (pin "60") (pinfunction "PD13_60") (pintype "bidirectional"))
    )
    (net (code "63") (name "/PE2") (class "Default")
      (node (ref "J9") (pin "2") (pinfunction "CS/D3_2") (pintype "bidirectional"))
      (node (ref "U1") (pin "1") (pinfunction "PE2_1") (pintype "bidirectional"))
    )
    (net (code "64") (name "/PE3") (class "Default")
      (node (ref "J12") (pin "3") (pinfunction "3_3") (pintype "bidirectional"))
      (node (ref "U1") (pin "2") (pinfunction "PE3_2") (pintype "bidirectional"))
    )
    (net (code "65") (name "/PE4") (class "Default")
      (node (ref "J6") (pin "3") (pinfunction "3_3") (pintype "bidirectional"))
      (node (ref "U1") (pin "3") (pinfunction "PE4_3") (pintype "bidirectional"))
    )
    (net (code "66") (name "/PE5") (class "Default")
      (node (ref "J6") (pin "4") (pinfunction "4_4") (pintype "bidirectional"))
      (node (ref "U1") (pin "4") (pinfunction "PE5_4") (pintype "bidirectional"))
    )
    (net (code "67") (name "/PE6") (class "Default")
      (node (ref "J6") (pin "5") (pinfunction "5_5") (pintype "bidirectional"))
      (node (ref "U1") (pin "5") (pinfunction "PE6_5") (pintype "bidirectional"))
    )
    (net (code "68") (name "/PFBOUT") (class "Default")
      (node (ref "C50") (pin "1") (pinfunction "1_1") (pintype "passive"))
      (node (ref "C53") (pin "2") (pinfunction "2_2") (pintype "passive"))
      (node (ref "C54") (pin "2") (pinfunction "2_2") (pintype "passive"))
      (node (ref "C55") (pin "+") (pinfunction "+_+") (pintype "passive"))
      (node (ref "IC5") (pin "16") (pinfunction "PFBIN1_16") (pintype "passive"))
      (node (ref "IC5") (pin "19") (pinfunction "PFBOUT_19") (pintype "passive"))
      (node (ref "IC5") (pin "30") (pinfunction "PFBIN2_30") (pintype "passive"))
    )
    (net (code "69") (name "/RD+") (class "Default")
      (node (ref "IC5") (pin "12") (pinfunction "RD+_12") (pintype "bidirectional"))
      (node (ref "R10") (pin "2") (pinfunction "2_2") (pintype "passive"))
      (node (ref "U3") (pin "14") (pinfunction "14_14") (pintype "bidirectional"))
    )
    (net (code "70") (name "/RD-") (class "Default")
      (node (ref "IC5") (pin "11") (pinfunction "RD-_11") (pintype "bidirectional"))
      (node (ref "R11") (pin "1") (pinfunction "1_1") (pintype "passive"))
      (node (ref "U3") (pin "16") (pinfunction "16_16") (pintype "bidirectional"))
    )
    (net (code "71") (name "/RESET") (class "Default")
      (node (ref "IC2") (pin "8") (pinfunction "TGT_NRESET_8") (pintype "bidirectional"))
      (node (ref "J11") (pin "3") (pinfunction "3_3") (pintype "bidirectional"))
      (node (ref "R24") (pin "1") (pinfunction "1_1") (pintype "passive"))
      (node (ref "U1") (pin "14") (pinfunction "NRST_14") (pintype "bidirectional"))
    )
    (net (code "72") (name "/RX+") (class "Default")
      (node (ref "J7") (pin "3") (pinfunction "3_3") (pintype "bidirectional"))
      (node (ref "U3") (pin "3") (pinfunction "3_3") (pintype "bidirectional"))
    )
    (net (code "73") (name "/RX-") (class "Default")
      (node (ref "J7") (pin "6") (pinfunction "6_6") (pintype "bidirectional"))
      (node (ref "U3") (pin "1") (pinfunction "1_1") (pintype "bidirectional"))
    )
    (net (code "74") (name "/SDIO_CK") (class "Default")
      (node (ref "J13") (pin "5") (pinfunction "5_5") (pintype "bidirectional"))
      (node (ref "U1") (pin "80") (pinfunction "PC12_80") (pintype "bidirectional"))
    )
    (net (code "75") (name "/SDIO_CMD") (class "Default")
      (node (ref "J13") (pin "6") (pinfunction "6_6") (pintype "bidirectional"))
      (node (ref "U1") (pin "83") (pinfunction "PD2_83") (pintype "bidirectional"))
    )
    (net (code "76") (name "/SDIO_D0") (class "Default")
      (node (ref "J13") (pin "1") (pinfunction "1_1") (pintype "bidirectional"))
      (node (ref "U1") (pin "65") (pinfunction "PC8_65") (pintype "bidirectional"))
    )
    (net (code "77") (name "/SDIO_D1") (class "Default")
      (node (ref "J13") (pin "2") (pinfunction "2_2") (pintype "bidirectional"))
      (node (ref "U1") (pin "66") (pinfunction "PC9_66") (pintype "bidirectional"))
    )
    (net (code "78") (name "/SDIO_D2") (class "Default")
      (node (ref "J13") (pin "3") (pinfunction "3_3") (pintype "bidirectional"))
      (node (ref "U1") (pin "78") (pinfunction "PC10_78") (pintype "bidirectional"))
    )
    (net (code "79") (name "/SDIO_D3") (class "Default")
      (node (ref "J13") (pin "4") (pinfunction "4_4") (pintype "bidirectional"))
      (node (ref "U1") (pin "79") (pinfunction "PC11_79") (pintype "bidirectional"))
    )
    (net (code "80") (name "/SPI2_MISO") (class "Default")
      (node (ref "J12") (pin "1") (pinfunction "1_1") (pintype "bidirectional"))
      (node (ref "J9") (pin "7") (pinfunction "DO/D0_7") (pintype "bidirectional"))
      (node (ref "U1") (pin "17") (pinfunction "PC2_17") (pintype "bidirectional"))
    )
    (net (code "81") (name "/SPI2_MOSI") (class "Default")
      (node (ref "J12") (pin "5") (pinfunction "5_5") (pintype "bidirectional"))
      (node (ref "J9") (pin "3") (pinfunction "DI/CMD_3") (pintype "bidirectional"))
      (node (ref "U1") (pin "18") (pinfunction "PC3_18") (pintype "bidirectional"))
    )
    (net (code "82") (name "/SPI2_SCK") (class "Default")
      (node (ref "J12") (pin "2") (pinfunction "2_2") (pintype "bidirectional"))
      (node (ref "J9") (pin "5") (pinfunction "CLK_5") (pintype "bidirectional"))
      (node (ref "U1") (pin "47") (pinfunction "PB10_47") (pintype "bidirectional"))
    )
    (net (code "83") (name "/SPI3_MISO") (class "Default")
      (node (ref "J1") (pin "6") (pinfunction "6_6") (pintype "bidirectional"))
      (node (ref "U1") (pin "90") (pinfunction "PB4_90") (pintype "bidirectional"))
    )
    (net (code "84") (name "/SPI3_MOSI") (class "Default")
      (node (ref "J1") (pin "7") (pinfunction "7_7") (pintype "bidirectional"))
      (node (ref "U1") (pin "91") (pinfunction "PB5_91") (pintype "bidirectional"))
    )
    (net (code "85") (name "/SPI3_NSS") (class "Default")
      (node (ref "J1") (pin "8") (pinfunction "8_8") (pintype "bidirectional"))
      (node (ref "U1") (pin "77") (pinfunction "PA15_77") (pintype "bidirectional"))
    )
    (net (code "86") (name "/SPI3_SCK") (class "Default")
      (node (ref "D5") (pin "-") (pinfunction "-_-") (pintype "passive"))
      (node (ref "J1") (pin "5") (pinfunction "5_5") (pintype "bidirectional"))
      (node (ref "U1") (pin "89") (pinfunction "PB3_89") (pintype "bidirectional"))
    )
    (net (code "87") (name "/SWCLK") (class "Default")
      (node (ref "IC2") (pin "16") (pinfunction "TGT_SWCLK_16") (pintype "bidirectional"))
      (node (ref "R45") (pin "2") (pinfunction "2_2") (pintype "passive"))
      (node (ref "U1") (pin "76") (pinfunction "PA14_76") (pintype "bidirectional"))
    )
    (net (code "88") (name "/SWDIO") (class "Default")
      (node (ref "IC2") (pin "17") (pinfunction "TGT_SWDIO_17") (pintype "bidirectional"))
      (node (ref "R44") (pin "1") (pinfunction "1_1") (pintype "passive"))
      (node (ref "U1") (pin "72") (pinfunction "PA13_72") (pintype "bidirectional"))
    )
    (net (code "89") (name "/TD+") (class "Default")
      (node (ref "IC5") (pin "15") (pinfunction "TD+_15") (pintype "bidirectional"))
      (node (ref "R8") (pin "2") (pinfunction "2_2") (pintype "passive"))
      (node (ref "U3") (pin "9") (pinfunction "9_9") (pintype "bidirectional"))
    )
    (net (code "90") (name "/TD-") (class "Default")
      (node (ref "IC5") (pin "14") (pinfunction "TD-_14") (pintype "bidirectional"))
      (node (ref "R9") (pin "1") (pinfunction "1_1") (pintype "passive"))
      (node (ref "U3") (pin "11") (pinfunction "11_11") (pintype "bidirectional"))
    )
    (net (code "91") (name "/TGT_D+") (class "Default")
      (node (ref "D11") (pin "1") (pinfunction "1_1") (pintype "bidirectional"))
      (node (ref "J8") (pin "3") (pinfunction "DP_3") (pintype "bidirectional"))
      (node (ref "R13") (pin "2") (pinfunction "2_2") (pintype "passive"))
      (node (ref "R36") (pin "2") (pinfunction "2_2") (pintype "passive"))
    )
    (net (code "92") (name "/TGT_D-") (class "Default")
      (node (ref "D11") (pin "2") (pinfunction "2_2") (pintype "bidirectional"))
      (node (ref "J8") (pin "2") (pinfunction "DM_2") (pintype "bidirectional"))
      (node (ref "R14") (pin "2") (pinfunction "2_2") (pintype "passive"))
    )
    (net (code "93") (name "/TX+") (class "Default")
      (node (ref "J7") (pin "1") (pinfunction "1_1") (pintype "bidirectional"))
      (node (ref "U3") (pin "8") (pinfunction "8_8") (pintype "bidirectional"))
    )
    (net (code "94") (name "/TX-") (class "Default")
      (node (ref "J7") (pin "2") (pinfunction "2_2") (pintype "bidirectional"))
      (node (ref "U3") (pin "6") (pinfunction "6_6") (pintype "bidirectional"))
    )
    (net (code "95") (name "/USART1_RX") (class "Default")
      (node (ref "J4") (pin "8") (pinfunction "8_8") (pintype "bidirectional"))
      (node (ref "U1") (pin "93") (pinfunction "PB7_93") (pintype "bidirectional"))
    )
    (net (code "96") (name "/USART1_TX") (class "Default")
      (node (ref "J4") (pin "7") (pinfunction "7_7") (pintype "bidirectional"))
      (node (ref "U1") (pin "92") (pinfunction "PB6_92") (pintype "bidirectional"))
    )
    (net (code "97") (name "/USART6_RX") (class "Default")
      (node (ref "J6") (pin "8") (pinfunction "8_8") (pintype "bidirectional"))
      (node (ref "P10") (pin "1") (pinfunction "1_1") (pintype "bidirectional"))
      (node (ref "U1") (pin "64") (pinfunction "PC7_64") (pintype "bidirectional"))
    )
    (net (code "98") (name "/USART6_TX") (class "Default")
      (node (ref "J6") (pin "7") (pinfunction "7_7") (pintype "bidirectional"))
      (node (ref "P9") (pin "2") (pinfunction "2_2") (pintype "bidirectional"))
      (node (ref "U1") (pin "63") (pinfunction "PC6_63") (pintype "bidirectional"))
    )
    (net (code "99") (name "/USB5V") (class "Default")
      (node (ref "5V") (pin "T") (pinfunction "T_T") (pintype "bidirectional"))
      (node (ref "C14") (pin "+") (pinfunction "+_+") (pintype "passive"))
      (node (ref "F1") (pin "2") (pinfunction "2_2") (pintype "bidirectional"))
      (node (ref "F3") (pin "2") (pinfunction "2_2") (pintype "bidirectional"))
      (node (ref "R12") (pin "2") (pinfunction "2_2") (pintype "passive"))
      (node (ref "R18") (pin "2") (pinfunction "2_2") (pintype "passive"))
      (node (ref "U2") (pin "3") (pinfunction "IN_3") (pintype "bidirectional"))
    )
    (net (code "100") (name "/VCAP1") (class "Default")
      (node (ref "C23") (pin "2") (pinfunction "2_2") (pintype "passive"))
      (node (ref "U1") (pin "49") (pinfunction "VCAP_1_49") (pintype "bidirectional"))
    )
    (net (code "101") (name "/VCAP2") (class "Default")
      (node (ref "C24") (pin "2") (pinfunction "2_2") (pintype "passive"))
      (node (ref "U1") (pin "73") (pinfunction "VCAP_2_73") (pintype "bidirectional"))
    )
    (net (code "102") (name "/VIN") (class "Default")
      (node (ref "J11") (pin "8") (pinfunction "8_8") (pintype "bidirectional"))
    )
    (net (code "103") (name "AREF") (class "Default")
      (node (ref "C36") (pin "2") (pinfunction "2_2") (pintype "passive"))
      (node (ref "C37") (pin "2") (pinfunction "2_2") (pintype "passive"))
      (node (ref "J1") (pin "3") (pinfunction "3_3") (pintype "bidirectional"))
      (node (ref "R25") (pin "1") (pinfunction "1_1") (pintype "passive"))
      (node (ref "U1") (pin "21") (pinfunction "VREF+_21") (pintype "bidirectional"))
    )
    (net (code "104") (name "GND_POWER") (class "Default")
      (node (ref "C1") (pin "1") (pinfunction "1_1") (pintype "passive"))
      (node (ref "C10") (pin "1") (pinfunction "1_1") (pintype "passive"))
      (node (ref "C11") (pin "2") (pinfunction "2_2") (pintype "passive"))
      (node (ref "C12") (pin "2") (pinfunction "2_2") (pintype "passive"))
      (node (ref "C13") (pin "-") (pinfunction "-_-") (pintype "passive"))
      (node (ref "C14") (pin "-") (pinfunction "-_-") (pintype "passive"))
      (node (ref "C15") (pin "1") (pinfunction "1_1") (pintype "passive"))
      (node (ref "C16") (pin "1") (pinfunction "1_1") (pintype "passive"))
      (node (ref "C17") (pin "1") (pinfunction "1_1") (pintype "passive"))
      (node (ref "C18") (pin "1") (pinfunction "1_1") (pintype "passive"))
      (node (ref "C19") (pin "1") (pinfunction "1_1") (pintype "passive"))
      (node (ref "C2") (pin "1") (pinfunction "1_1") (pintype "passive"))
      (node (ref "C20") (pin "1") (pinfunction "1_1") (pintype "passive"))
      (node (ref "C21") (pin "1") (pinfunction "1_1") (pintype "passive"))
      (node (ref "C22") (pin "2") (pinfunction "2_2") (pintype "passive"))
      (node (ref "C23") (pin "1") (pinfunction "1_1") (pintype "passive"))
      (node (ref "C24") (pin "1") (pinfunction "1_1") (pintype "passive"))
      (node (ref "C25") (pin "1") (pinfunction "1_1") (pintype "passive"))
      (node (ref "C26") (pin "1") (pinfunction "1_1") (pintype "passive"))
      (node (ref "C27") (pin "1") (pinfunction "1_1") (pintype "passive"))
      (node (ref "C28") (pin "1") (pinfunction "1_1") (pintype "passive"))
      (node (ref "C29") (pin "1") (pinfunction "1_1") (pintype "passive"))
      (node (ref "C3") (pin "2") (pinfunction "2_2") (pintype "passive"))
      (node (ref "C30") (pin "1") (pinfunction "1_1") (pintype "passive"))
      (node (ref "C31") (pin "1") (pinfunction "1_1") (pintype "passive"))
      (node (ref "C33") (pin "1") (pinfunction "1_1") (pintype "passive"))
      (node (ref "C36") (pin "1") (pinfunction "1_1") (pintype "passive"))
      (node (ref "C37") (pin "1") (pinfunction "1_1") (pintype "passive"))
      (node (ref "C4") (pin "2") (pinfunction "2_2") (pintype "passive"))
      (node (ref "C45") (pin "1") (pinfunction "1_1") (pintype "passive"))
      (node (ref "C46") (pin "1") (pinfunction "1_1") (pintype "passive"))
      (node (ref "C47") (pin "2") (pinfunction "2_2") (pintype "passive"))
      (node (ref "C48") (pin "2") (pinfunction "2_2") (pintype "passive"))
      (node (ref "C5") (pin "2") (pinfunction "2_2") (pintype "passive"))
      (node (ref "C50") (pin "2") (pinfunction "2_2") (pintype "passive"))
      (node (ref "C53") (pin "1") (pinfunction "1_1") (pintype "passive"))
      (node (ref "C54") (pin "1") (pinfunction "1_1") (pintype "passive"))
      (node (ref "C55") (pin "-") (pinfunction "-_-") (pintype "passive"))
      (node (ref "C6") (pin "2") (pinfunction "2_2") (pintype "passive"))
      (node (ref "C7") (pin "2") (pinfunction "2_2") (pintype "passive"))
      (node (ref "C8") (pin "2") (pinfunction "2_2") (pintype "passive"))
      (node (ref "C9") (pin "-") (pinfunction "-_-") (pintype "passive"))
      (node (ref "D11") (pin "3") (pinfunction "3_3") (pintype "bidirectional"))
      (node (ref "D13") (pin "3") (pinfunction "3_3") (pintype "bidirectional"))
      (node (ref "GND") (pin "T") (pinfunction "T_T") (pintype "bidirectional"))
      (node (ref "IC2") (pin "EXP") (pinfunction "VSS_EXP") (pintype "bidirectional"))
      (node (ref "IC5") (pin "13") (pinfunction "AGND_13") (pintype "power_in"))
      (node (ref "IC5") (pin "17") (pinfunction "AGND_17") (pintype "power_in"))
      (node (ref "IC5") (pin "29") (pinfunction "DGND_29") (pintype "power_in"))
      (node (ref "IC5") (pin "40") (pinfunction "IOGND_40") (pintype "power_in"))
      (node (ref "IC5") (pin "DAP") (pinfunction "GNDPAD_DAP") (pintype "power_in"))
      (node (ref "J1") (pin "4") (pinfunction "4_4") (pintype "bidirectional"))
      (node (ref "J10") (pin "5") (pinfunction "GND_5") (pintype "bidirectional"))
      (node (ref "J10") (pin "P1") (pinfunction "GND_P1") (pintype "bidirectional"))
      (node (ref "J10") (pin "P2") (pinfunction "GND_P2") (pintype "bidirectional"))
      (node (ref "J10") (pin "P3") (pinfunction "GND_P3") (pintype "bidirectional"))
      (node (ref "J10") (pin "P4") (pinfunction "GND_P4") (pintype "bidirectional"))
      (node (ref "J11") (pin "6") (pinfunction "6_6") (pintype "bidirectional"))
      (node (ref "J11") (pin "7") (pinfunction "7_7") (pintype "bidirectional"))
      (node (ref "J12") (pin "4") (pinfunction "4_4") (pintype "bidirectional"))
      (node (ref "J2") (pin "18") (pinfunction "18_18") (pintype "bidirectional"))
      (node (ref "J2") (pin "19") (pinfunction "19_19") (pintype "bidirectional"))
      (node (ref "J2") (pin "32") (pinfunction "32_32") (pintype "bidirectional"))
      (node (ref "J7") (pin "13") (pinfunction "13_13") (pintype "bidirectional"))
      (node (ref "J7") (pin "14") (pinfunction "14_14") (pintype "bidirectional"))
      (node (ref "J8") (pin "5") (pinfunction "GND_5") (pintype "bidirectional"))
      (node (ref "J8") (pin "S1") (pinfunction "GND_S1") (pintype "bidirectional"))
      (node (ref "J8") (pin "S2") (pinfunction "GND_S2") (pintype "bidirectional"))
      (node (ref "J8") (pin "S3") (pinfunction "GND_S3") (pintype "bidirectional"))
      (node (ref "J8") (pin "S4") (pinfunction "GND_S4") (pintype "bidirectional"))
      (node (ref "J8") (pin "S5") (pinfunction "GND_S5") (pintype "bidirectional"))
      (node (ref "J8") (pin "S6") (pinfunction "GND_S6") (pintype "bidirectional"))
      (node (ref "J9") (pin "10") (pinfunction "G2_10") (pintype "bidirectional"))
      (node (ref "J9") (pin "11") (pinfunction "G3_11") (pintype "bidirectional"))
      (node (ref "J9") (pin "12") (pinfunction "G4_12") (pintype "bidirectional"))
      (node (ref "J9") (pin "6") (pinfunction "VSS_6") (pintype "bidirectional"))
      (node (ref "J9") (pin "9") (pinfunction "G1_9") (pintype "bidirectional"))
      (node (ref "R2") (pin "1") (pinfunction "1_1") (pintype "passive"))
      (node (ref "R26") (pin "1") (pinfunction "1_1") (pintype "passive"))
      (node (ref "R3") (pin "1") (pinfunction "1_1") (pintype "passive"))
      (node (ref "R40") (pin "1") (pinfunction "1_1") (pintype "passive"))
      (node (ref "R45") (pin "1") (pinfunction "1_1") (pintype "passive"))
      (node (ref "R59") (pin "2") (pinfunction "2_2") (pintype "passive"))
      (node (ref "R7") (pin "1") (pinfunction "1_1") (pintype "passive"))
      (node (ref "SW1") (pin "1") (pinfunction "1_1") (pintype "bidirectional"))
      (node (ref "SW1") (pin "S1") (pinfunction "S1_S1") (pintype "bidirectional"))
      (node (ref "SW1") (pin "S2") (pinfunction "S2_S2") (pintype "bidirectional"))
      (node (ref "U1") (pin "10") (pinfunction "VSS_10") (pintype "bidirectional"))
      (node (ref "U1") (pin "20") (pinfunction "VSSA_20") (pintype "bidirectional"))
      (node (ref "U1") (pin "27") (pinfunction "VSS_27") (pintype "bidirectional"))
      (node (ref "U1") (pin "74") (pinfunction "VSS_74") (pintype "bidirectional"))
      (node (ref "U1") (pin "99") (pinfunction "VSS_99") (pintype "bidirectional"))
      (node (ref "U2") (pin "1") (pinfunction "GND_1") (pintype "bidirectional"))
      (node (ref "X1") (pin "2") (pinfunction "GND_2") (pintype "bidirectional"))
      (node (ref "X4") (pin "2") (pinfunction "2_2") (pintype "passive"))
    )
    (net (code "105") (name "Net-(C10-Pad2)") (class "Default")
      (node (ref "C10") (pin "2") (pinfunction "2_2") (pintype "passive"))
      (node (ref "R60") (pin "1") (pinfunction "1_1") (pintype "passive"))
      (node (ref "R61") (pin "1") (pinfunction "1_1") (pintype "passive"))
    )
    (net (code "106") (name "Net-(C13-Pad+)") (class "Default")
      (node (ref "C13") (pin "+") (pinfunction "+_+") (pintype "passive"))
      (node (ref "C18") (pin "2") (pinfunction "2_2") (pintype "passive"))
      (node (ref "PWR") (pin "+") (pinfunction "+_+") (pintype "passive"))
      (node (ref "R33") (pin "1") (pinfunction "1_1") (pintype "passive"))
      (node (ref "R35") (pin "2") (pinfunction "2_2") (pintype "passive"))
      (node (ref "U2") (pin "2") (pinfunction "OUT_2") (pintype "bidirectional"))
      (node (ref "U2") (pin "TER") (pinfunction "OUT_TER") (pintype "bidirectional"))
    )
    (net (code "107") (name "Net-(D5-Pad+)") (class "Default")
      (node (ref "D5") (pin "+") (pinfunction "+_+") (pintype "passive"))
      (node (ref "R1") (pin "1") (pinfunction "1_1") (pintype "passive"))
    )
    (net (code "108") (name "Net-(D21-Pad+)") (class "Default")
      (node (ref "D21") (pin "+") (pinfunction "+_+") (pintype "passive"))
      (node (ref "R41") (pin "1") (pinfunction "1_1") (pintype "passive"))
    )
    (net (code "109") (name "Net-(D22-Pad+)") (class "Default")
      (node (ref "D22") (pin "+") (pinfunction "+_+") (pintype "passive"))
      (node (ref "R42") (pin "1") (pinfunction "1_1") (pintype "passive"))
    )
    (net (code "110") (name "Net-(D23-Pad+)") (class "Default")
      (node (ref "D23") (pin "+") (pinfunction "+_+") (pintype "passive"))
      (node (ref "R43") (pin "1") (pinfunction "1_1") (pintype "passive"))
    )
    (net (code "111") (name "Net-(IC2-IF_NRESET)") (class "Default")
      (node (ref "C31") (pin "2") (pinfunction "2_2") (pintype "passive"))
      (node (ref "IC2") (pin "2") (pinfunction "IF_NRESET_2") (pintype "bidirectional"))
      (node (ref "R39") (pin "1") (pinfunction "1_1") (pintype "passive"))
      (node (ref "RST") (pin "T") (pinfunction "T_T") (pintype "bidirectional"))
    )
    (net (code "112") (name "Net-(IC2-LED_HID)") (class "Default")
      (node (ref "D22") (pin "-") (pinfunction "-_-") (pintype "passive"))
      (node (ref "IC2") (pin "12") (pinfunction "LED_HID_12") (pintype "bidirectional"))
    )
    (net (code "113") (name "Net-(IC2-LED_MSD)") (class "Default")
      (node (ref "D21") (pin "-") (pinfunction "-_-") (pintype "passive"))
      (node (ref "IC2") (pin "7") (pinfunction "LED_MSD_7") (pintype "bidirectional"))
    )
    (net (code "114") (name "Net-(IC2-LED_UART)") (class "Default")
      (node (ref "D23") (pin "-") (pinfunction "-_-") (pintype "passive"))
      (node (ref "IC2") (pin "21") (pinfunction "LED_UART_21") (pintype "bidirectional"))
    )
    (net (code "115") (name "Net-(IC2-NRESET_FB_BL)") (class "Default")
      (node (ref "IC2") (pin "1") (pinfunction "NRESET_FB_BL_1") (pintype "bidirectional"))
      (node (ref "IC2") (pin "3") (pinfunction "NRESET_FB_ISP_3") (pintype "bidirectional"))
      (node (ref "R5") (pin "1") (pinfunction "1_1") (pintype "passive"))
      (node (ref "SW1") (pin "2") (pinfunction "2_2") (pintype "bidirectional"))
    )
    (net (code "116") (name "Net-(IC2-USB_D+)") (class "Default")
      (node (ref "IC2") (pin "14") (pinfunction "USB_D+_14") (pintype "bidirectional"))
      (node (ref "R13") (pin "1") (pinfunction "1_1") (pintype "passive"))
    )
    (net (code "117") (name "Net-(IC2-USB_D-)") (class "Default")
      (node (ref "IC2") (pin "13") (pinfunction "USB_D-_13") (pintype "bidirectional"))
      (node (ref "R14") (pin "1") (pinfunction "1_1") (pintype "passive"))
    )
    (net (code "118") (name "Net-(IC2-USB_SCON)") (class "Default")
      (node (ref "IC2") (pin "15") (pinfunction "USB_SCON_15") (pintype "bidirectional"))
      (node (ref "Q7") (pin "1") (pinfunction "G_1") (pintype "passive"))
      (node (ref "R37") (pin "1") (pinfunction "1_1") (pintype "passive"))
    )
    (net (code "119") (name "Net-(IC2-USB_VBUS)") (class "Default")
      (node (ref "IC2") (pin "9") (pinfunction "USB_VBUS_9") (pintype "bidirectional"))
      (node (ref "R12") (pin "1") (pinfunction "1_1") (pintype "passive"))
      (node (ref "R40") (pin "2") (pinfunction "2_2") (pintype "passive"))
    )
    (net (code "120") (name "Net-(IC2-XTALIN)") (class "Default")
      (node (ref "C15") (pin "2") (pinfunction "2_2") (pintype "passive"))
      (node (ref "IC2") (pin "4") (pinfunction "XTALIN_4") (pintype "bidirectional"))
      (node (ref "X2") (pin "2") (pinfunction "2_2") (pintype "passive"))
    )
    (net (code "121") (name "Net-(IC2-XTALOUT)") (class "Default")
      (node (ref "C17") (pin "2") (pinfunction "2_2") (pintype "passive"))
      (node (ref "IC2") (pin "5") (pinfunction "XTALOUT_5") (pintype "bidirectional"))
      (node (ref "X2") (pin "1") (pinfunction "1_1") (pintype "passive"))
    )
    (net (code "122") (name "Net-(IC5-RBIAS)") (class "Default")
      (node (ref "IC5") (pin "20") (pinfunction "RBIAS_20") (pintype "passive"))
      (node (ref "R59") (pin "1") (pinfunction "1_1") (pintype "passive"))
    )
    (net (code "123") (name "Net-(IC5-RESET_N)") (class "Default")
      (node (ref "IC5") (pin "23") (pinfunction "RESET_N_23") (pintype "input"))
      (node (ref "P1") (pin "2") (pinfunction "2_2") (pintype "bidirectional"))
    )
    (net (code "124") (name "Net-(IC5-RX_DV{slash}MII_MODE)") (class "Default")
      (node (ref "IC5") (pin "32") (pinfunction "RX_DV/MII_MODE_32") (pintype "output"))
      (node (ref "R58") (pin "2") (pinfunction "2_2") (pintype "passive"))
    )
    (net (code "125") (name "Net-(J7-G-)") (class "Default")
      (node (ref "J7") (pin "9") (pinfunction "G-_9") (pintype "bidirectional"))
      (node (ref "R2") (pin "2") (pinfunction "2_2") (pintype "passive"))
    )
    (net (code "126") (name "Net-(J7-Y+)") (class "Default")
      (node (ref "J7") (pin "12") (pinfunction "Y+_12") (pintype "bidirectional"))
      (node (ref "R4") (pin "2") (pinfunction "2_2") (pintype "passive"))
    )
    (net (code "127") (name "Net-(J8-VCC)") (class "Default")
      (node (ref "C7") (pin "1") (pinfunction "1_1") (pintype "passive"))
      (node (ref "C8") (pin "1") (pinfunction "1_1") (pintype "passive"))
      (node (ref "F3") (pin "1") (pinfunction "1_1") (pintype "bidirectional"))
      (node (ref "J8") (pin "1") (pinfunction "VCC_1") (pintype "bidirectional"))
    )
    (net (code "128") (name "Net-(J10-DM)") (class "Default")
      (node (ref "D13") (pin "2") (pinfunction "2_2") (pintype "bidirectional"))
      (node (ref "J10") (pin "2") (pinfunction "DM_2") (pintype "bidirectional"))
      (node (ref "R16") (pin "2") (pinfunction "2_2") (pintype "passive"))
    )
    (net (code "129") (name "Net-(J10-DP)") (class "Default")
      (node (ref "D13") (pin "1") (pinfunction "1_1") (pintype "bidirectional"))
      (node (ref "J10") (pin "3") (pinfunction "DP_3") (pintype "bidirectional"))
      (node (ref "R15") (pin "2") (pinfunction "2_2") (pintype "passive"))
    )
    (net (code "130") (name "Net-(J10-VCC)") (class "Default")
      (node (ref "C11") (pin "1") (pinfunction "1_1") (pintype "passive"))
      (node (ref "C12") (pin "1") (pinfunction "1_1") (pintype "passive"))
      (node (ref "F1") (pin "1") (pinfunction "1_1") (pintype "bidirectional"))
      (node (ref "J10") (pin "1") (pinfunction "VCC_1") (pintype "bidirectional"))
    )
    (net (code "131") (name "Net-(J12-Pad6)") (class "Default")
      (node (ref "J12") (pin "6") (pinfunction "6_6") (pintype "bidirectional"))
      (node (ref "R17") (pin "1") (pinfunction "1_1") (pintype "passive"))
    )
    (net (code "132") (name "Net-(PWR-Pad-)") (class "Default")
      (node (ref "PWR") (pin "-") (pinfunction "-_-") (pintype "passive"))
      (node (ref "R26") (pin "2") (pinfunction "2_2") (pintype "passive"))
    )
    (net (code "133") (name "Net-(Q7-D)") (class "Default")
      (node (ref "Q7") (pin "3") (pinfunction "D_3") (pintype "passive"))
      (node (ref "R36") (pin "1") (pinfunction "1_1") (pintype "passive"))
    )
    (net (code "134") (name "Net-(R60-Pad2)") (class "Default")
      (node (ref "R60") (pin "2") (pinfunction "2_2") (pintype "passive"))
      (node (ref "U3") (pin "7") (pinfunction "7_7") (pintype "bidirectional"))
    )
    (net (code "135") (name "Net-(R61-Pad2)") (class "Default")
      (node (ref "R61") (pin "2") (pinfunction "2_2") (pintype "passive"))
      (node (ref "U3") (pin "2") (pinfunction "2_2") (pintype "bidirectional"))
    )
    (net (code "136") (name "Net-(U1-PH0)") (class "Default")
      (node (ref "C27") (pin "2") (pinfunction "2_2") (pintype "passive"))
      (node (ref "U1") (pin "12") (pinfunction "PH0_12") (pintype "bidirectional"))
      (node (ref "X4") (pin "1") (pinfunction "1_1") (pintype "passive"))
    )
    (net (code "137") (name "Net-(U1-PH1)") (class "Default")
      (node (ref "C28") (pin "2") (pinfunction "2_2") (pintype "passive"))
      (node (ref "U1") (pin "13") (pinfunction "PH1_13") (pintype "bidirectional"))
      (node (ref "X4") (pin "3") (pinfunction "3_3") (pintype "passive"))
    )
    (net (code "138") (name "Net-(X1-ENABLE)") (class "Default")
      (node (ref "P5") (pin "2") (pinfunction "2_2") (pintype "bidirectional"))
      (node (ref "X1") (pin "1") (pinfunction "ENABLE_1") (pintype "bidirectional"))
    )
    (net (code "139") (name "TGT_3V3") (class "Default")
      (node (ref "C1") (pin "2") (pinfunction "2_2") (pintype "passive"))
      (node (ref "C29") (pin "2") (pinfunction "2_2") (pintype "passive"))
      (node (ref "C30") (pin "2") (pinfunction "2_2") (pintype "passive"))
      (node (ref "IC2") (pin "29") (pinfunction "VDD2_29") (pintype "bidirectional"))
      (node (ref "IC2") (pin "6") (pinfunction "VDD1_6") (pintype "bidirectional"))
      (node (ref "I_3V3") (pin "T") (pinfunction "T_T") (pintype "bidirectional"))
      (node (ref "Q7") (pin "2") (pinfunction "S_2") (pintype "passive"))
      (node (ref "R33") (pin "2") (pinfunction "2_2") (pintype "passive"))
      (node (ref "R37") (pin "2") (pinfunction "2_2") (pintype "passive"))
      (node (ref "R39") (pin "2") (pinfunction "2_2") (pintype "passive"))
      (node (ref "R41") (pin "2") (pinfunction "2_2") (pintype "passive"))
      (node (ref "R42") (pin "2") (pinfunction "2_2") (pintype "passive"))
      (node (ref "R43") (pin "2") (pinfunction "2_2") (pintype "passive"))
      (node (ref "R44") (pin "2") (pinfunction "2_2") (pintype "passive"))
      (node (ref "R5") (pin "2") (pinfunction "2_2") (pintype "passive"))
    )
    (net (code "140") (name "VDDA") (class "Default")
      (node (ref "C21") (pin "2") (pinfunction "2_2") (pintype "passive"))
      (node (ref "C33") (pin "2") (pinfunction "2_2") (pintype "passive"))
      (node (ref "L2") (pin "1") (pinfunction "1_1") (pintype "passive"))
      (node (ref "R25") (pin "2") (pinfunction "2_2") (pintype "passive"))
      (node (ref "U1") (pin "22") (pinfunction "VDDA_22") (pintype "bidirectional"))
    )
    (net (code "141") (name "unconnected-(IC2-NC2-Pad10)") (class "Default")
      (node (ref "IC2") (pin "10") (pinfunction "NC2_10") (pintype "bidirectional"))
    )
    (net (code "142") (name "unconnected-(IC2-NC3-Pad11)") (class "Default")
      (node (ref "IC2") (pin "11") (pinfunction "NC3_11") (pintype "bidirectional"))
    )
    (net (code "143") (name "unconnected-(IC2-NC4-Pad19)") (class "Default")
      (node (ref "IC2") (pin "19") (pinfunction "NC4_19") (pintype "bidirectional"))
    )
    (net (code "144") (name "unconnected-(IC2-NC5-Pad20)") (class "Default")
      (node (ref "IC2") (pin "20") (pinfunction "NC5_20") (pintype "bidirectional"))
    )
    (net (code "145") (name "unconnected-(IC2-NC6-Pad22)") (class "Default")
      (node (ref "IC2") (pin "22") (pinfunction "NC6_22") (pintype "bidirectional"))
    )
    (net (code "146") (name "unconnected-(IC2-NC7-Pad23)") (class "Default")
      (node (ref "IC2") (pin "23") (pinfunction "NC7_23") (pintype "bidirectional"))
    )
    (net (code "147") (name "unconnected-(IC2-NC8-Pad24)") (class "Default")
      (node (ref "IC2") (pin "24") (pinfunction "NC8_24") (pintype "bidirectional"))
    )
    (net (code "148") (name "unconnected-(IC2-NC9-Pad25)") (class "Default")
      (node (ref "IC2") (pin "25") (pinfunction "NC9_25") (pintype "bidirectional"))
    )
    (net (code "149") (name "unconnected-(IC2-NC10-Pad28)") (class "Default")
      (node (ref "IC2") (pin "28") (pinfunction "NC10_28") (pintype "bidirectional"))
    )
    (net (code "150") (name "unconnected-(IC2-NC11-Pad30)") (class "Default")
      (node (ref "IC2") (pin "30") (pinfunction "NC11_30") (pintype "bidirectional"))
    )
    (net (code "151") (name "unconnected-(IC2-SLEEP_NREQ-Pad27)") (class "Default")
      (node (ref "IC2") (pin "27") (pinfunction "SLEEP_NREQ_27") (pintype "bidirectional"))
    )
    (net (code "152") (name "unconnected-(IC2-TGT_SWO-Pad18)") (class "Default")
      (node (ref "IC2") (pin "18") (pinfunction "TGT_SWO_18") (pintype "bidirectional"))
    )
    (net (code "153") (name "unconnected-(IC2-WAKE_NREQ-Pad26)") (class "Default")
      (node (ref "IC2") (pin "26") (pinfunction "WAKE_NREQ_26") (pintype "bidirectional"))
    )
    (net (code "154") (name "unconnected-(IC5-COL{slash}PHYAD0-Pad35)") (class "Default")
      (node (ref "IC5") (pin "35") (pinfunction "COL/PHYAD0_35") (pintype "output"))
    )
    (net (code "155") (name "unconnected-(IC5-RESERVED-Pad8)") (class "Default")
      (node (ref "IC5") (pin "8") (pinfunction "RESERVED_8") (pintype "no_connect"))
    )
    (net (code "156") (name "unconnected-(IC5-RESERVED-Pad9)") (class "Default")
      (node (ref "IC5") (pin "9") (pinfunction "RESERVED_9") (pintype "no_connect"))
    )
    (net (code "157") (name "unconnected-(IC5-RESERVED-Pad10)") (class "Default")
      (node (ref "IC5") (pin "10") (pinfunction "RESERVED_10") (pintype "no_connect"))
    )
    (net (code "158") (name "unconnected-(IC5-RXD_2{slash}PHYAD3-Pad38)") (class "Default")
      (node (ref "IC5") (pin "38") (pinfunction "RXD_2/PHYAD3_38") (pintype "output"))
    )
    (net (code "159") (name "unconnected-(IC5-RXD_3{slash}PHYAD4-Pad39)") (class "Default")
      (node (ref "IC5") (pin "39") (pinfunction "RXD_3/PHYAD4_39") (pintype "output"))
    )
    (net (code "160") (name "unconnected-(IC5-RX_CLK-Pad31)") (class "Default")
      (node (ref "IC5") (pin "31") (pinfunction "RX_CLK_31") (pintype "output"))
    )
    (net (code "161") (name "unconnected-(IC5-RX_ER{slash}MDIX_EN-Pad34)") (class "Default")
      (node (ref "IC5") (pin "34") (pinfunction "RX_ER/MDIX_EN_34") (pintype "output"))
    )
    (net (code "162") (name "unconnected-(IC5-TXD_2-Pad6)") (class "Default")
      (node (ref "IC5") (pin "6") (pinfunction "TXD_2_6") (pintype "bidirectional"))
    )
    (net (code "163") (name "unconnected-(IC5-TXD_3-Pad7)") (class "Default")
      (node (ref "IC5") (pin "7") (pinfunction "TXD_3_7") (pintype "bidirectional"))
    )
    (net (code "164") (name "unconnected-(IC5-TX_CLK-Pad2)") (class "Default")
      (node (ref "IC5") (pin "2") (pinfunction "TX_CLK_2") (pintype "output"))
    )
    (net (code "165") (name "unconnected-(IC5-X2-Pad27)") (class "Default")
      (node (ref "IC5") (pin "27") (pinfunction "X2_27") (pintype "passive"))
    )
    (net (code "166") (name "unconnected-(J7-Pad4)") (class "Default")
      (node (ref "J7") (pin "4") (pinfunction "4_4") (pintype "bidirectional"))
    )
    (net (code "167") (name "unconnected-(J7-Pad5)") (class "Default")
      (node (ref "J7") (pin "5") (pinfunction "5_5") (pintype "bidirectional"))
    )
    (net (code "168") (name "unconnected-(J7-Pad7)") (class "Default")
      (node (ref "J7") (pin "7") (pinfunction "7_7") (pintype "bidirectional"))
    )
    (net (code "169") (name "unconnected-(J7-Pad8)") (class "Default")
      (node (ref "J7") (pin "8") (pinfunction "8_8") (pintype "bidirectional"))
    )
    (net (code "170") (name "unconnected-(J8-ID-Pad4)") (class "Default")
      (node (ref "J8") (pin "4") (pinfunction "ID_4") (pintype "bidirectional"))
    )
    (net (code "171") (name "unconnected-(J9-RSV{slash}D1-Pad8)") (class "Default")
      (node (ref "J9") (pin "8") (pinfunction "RSV/D1_8") (pintype "bidirectional"))
    )
    (net (code "172") (name "unconnected-(J9-RSV{slash}D2-Pad1)") (class "Default")
      (node (ref "J9") (pin "1") (pinfunction "RSV/D2_1") (pintype "bidirectional"))
    )
    (net (code "173") (name "unconnected-(J11-Pad1)") (class "Default")
      (node (ref "J11") (pin "1") (pinfunction "1_1") (pintype "bidirectional"))
    )
    (net (code "174") (name "unconnected-(U1-PC14-Pad8)") (class "Default")
      (node (ref "U1") (pin "8") (pinfunction "PC14_8") (pintype "bidirectional"))
    )
    (net (code "175") (name "unconnected-(U1-PC15-Pad9)") (class "Default")
      (node (ref "U1") (pin "9") (pinfunction "PC15_9") (pintype "bidirectional"))
    )
    (net (code "176") (name "unconnected-(U3-Pad4)") (class "Default")
      (node (ref "U3") (pin "4") (pinfunction "4_4") (pintype "bidirectional"))
    )
    (net (code "177") (name "unconnected-(U3-Pad5)") (class "Default")
      (node (ref "U3") (pin "5") (pinfunction "5_5") (pintype "bidirectional"))
    )
    (net (code "178") (name "unconnected-(U3-Pad12)") (class "Default")
      (node (ref "U3") (pin "12") (pinfunction "12_12") (pintype "bidirectional"))
    )
    (net (code "179") (name "unconnected-(U3-Pad13)") (class "Default")
      (node (ref "U3") (pin "13") (pinfunction "13_13") (pintype "bidirectional"))
    )
  )
)
